# Roland_mem2.net
KiCad netlist of a schematic drawn in EAGLE
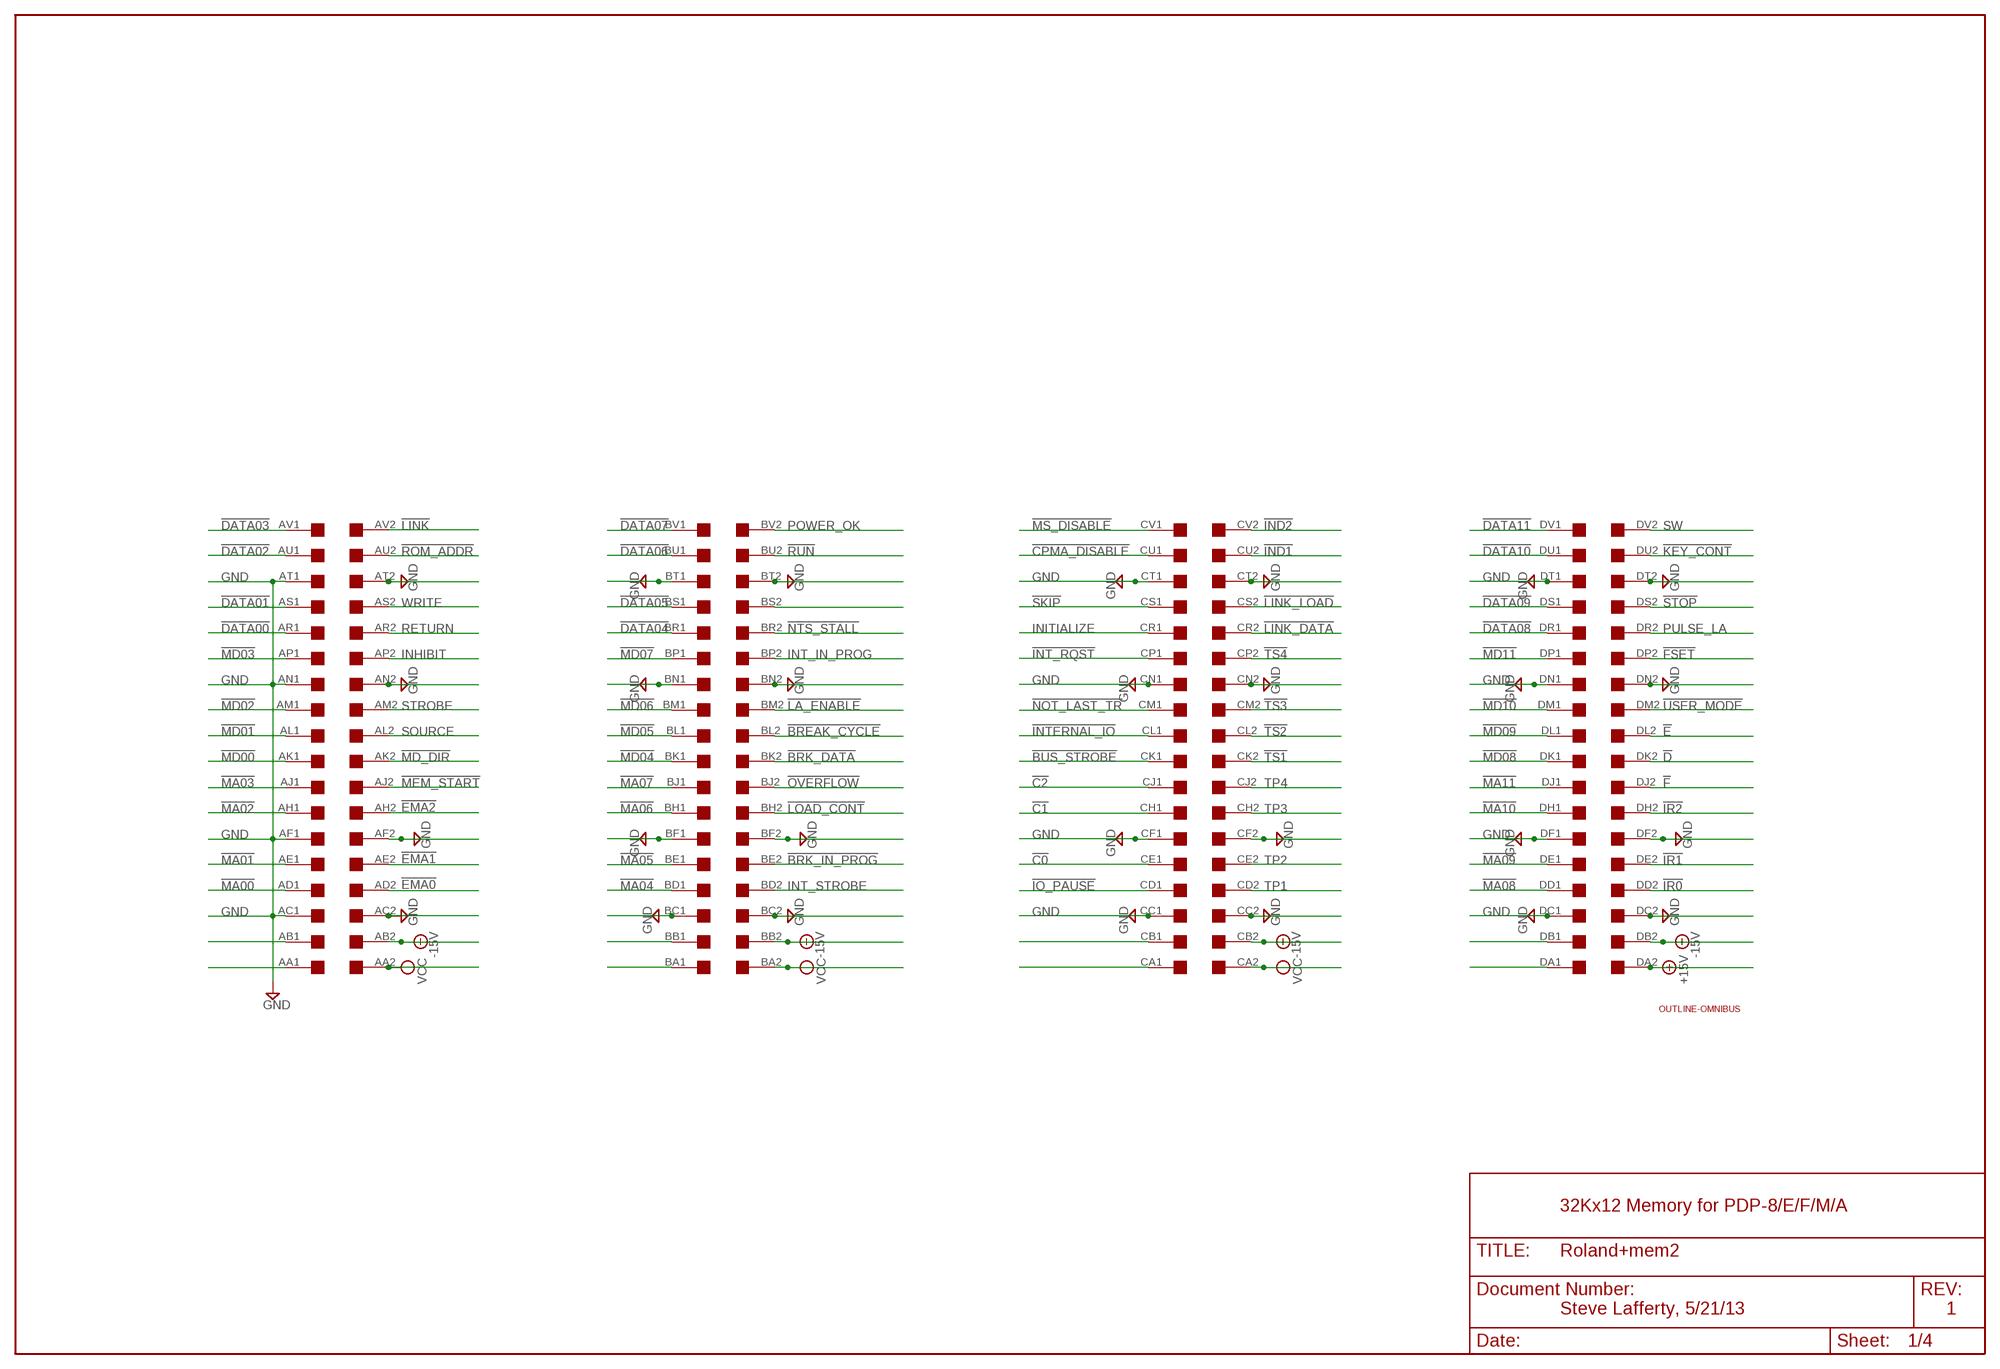
[diagram p0: schematic, sheet 1]
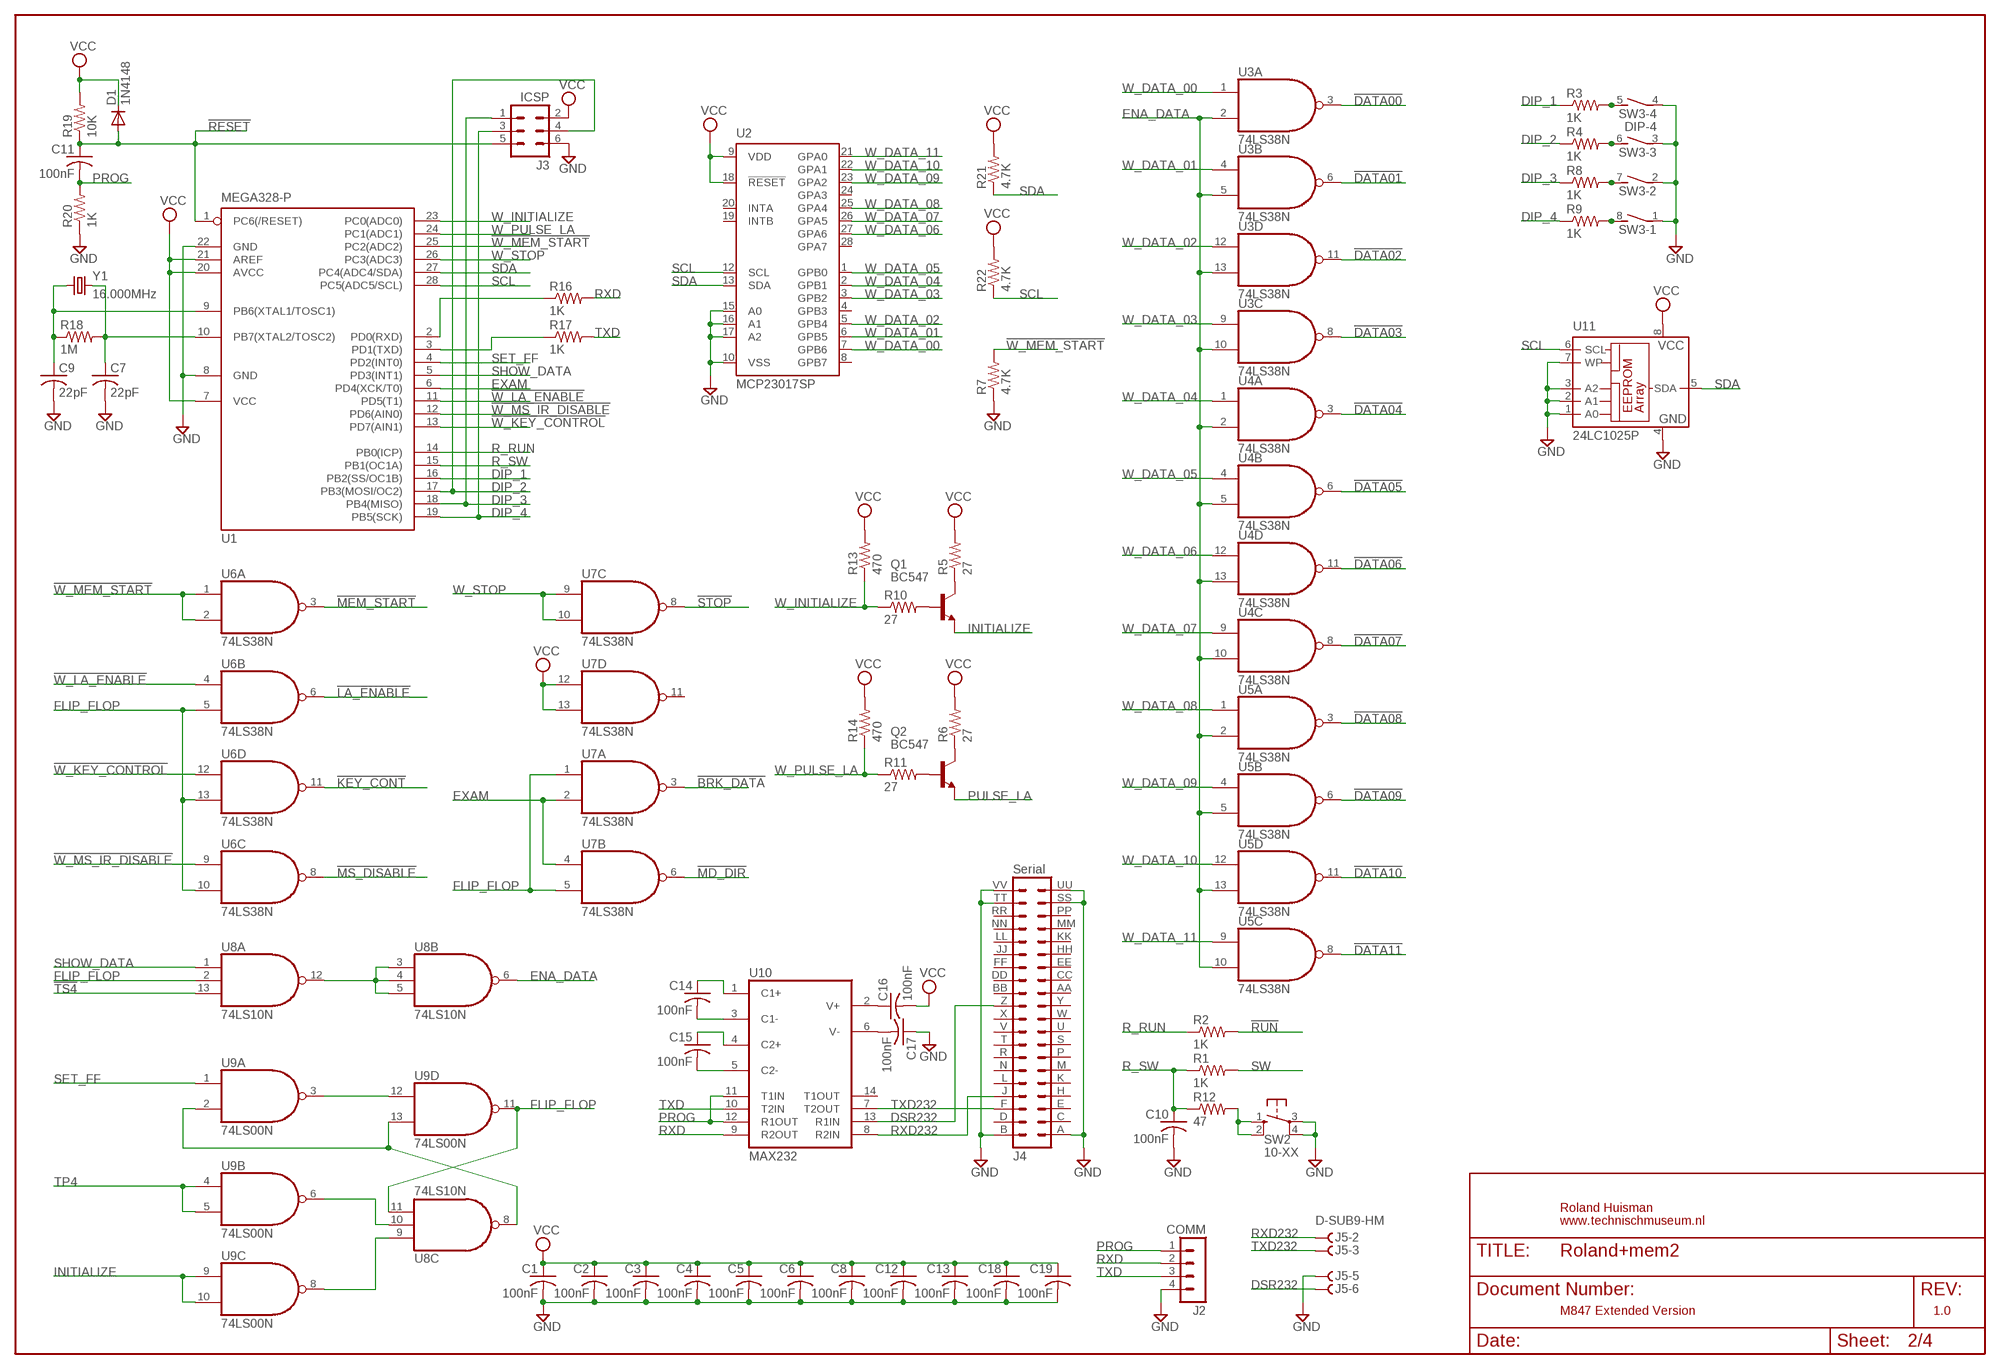
[diagram p1: schematic, sheet 2]
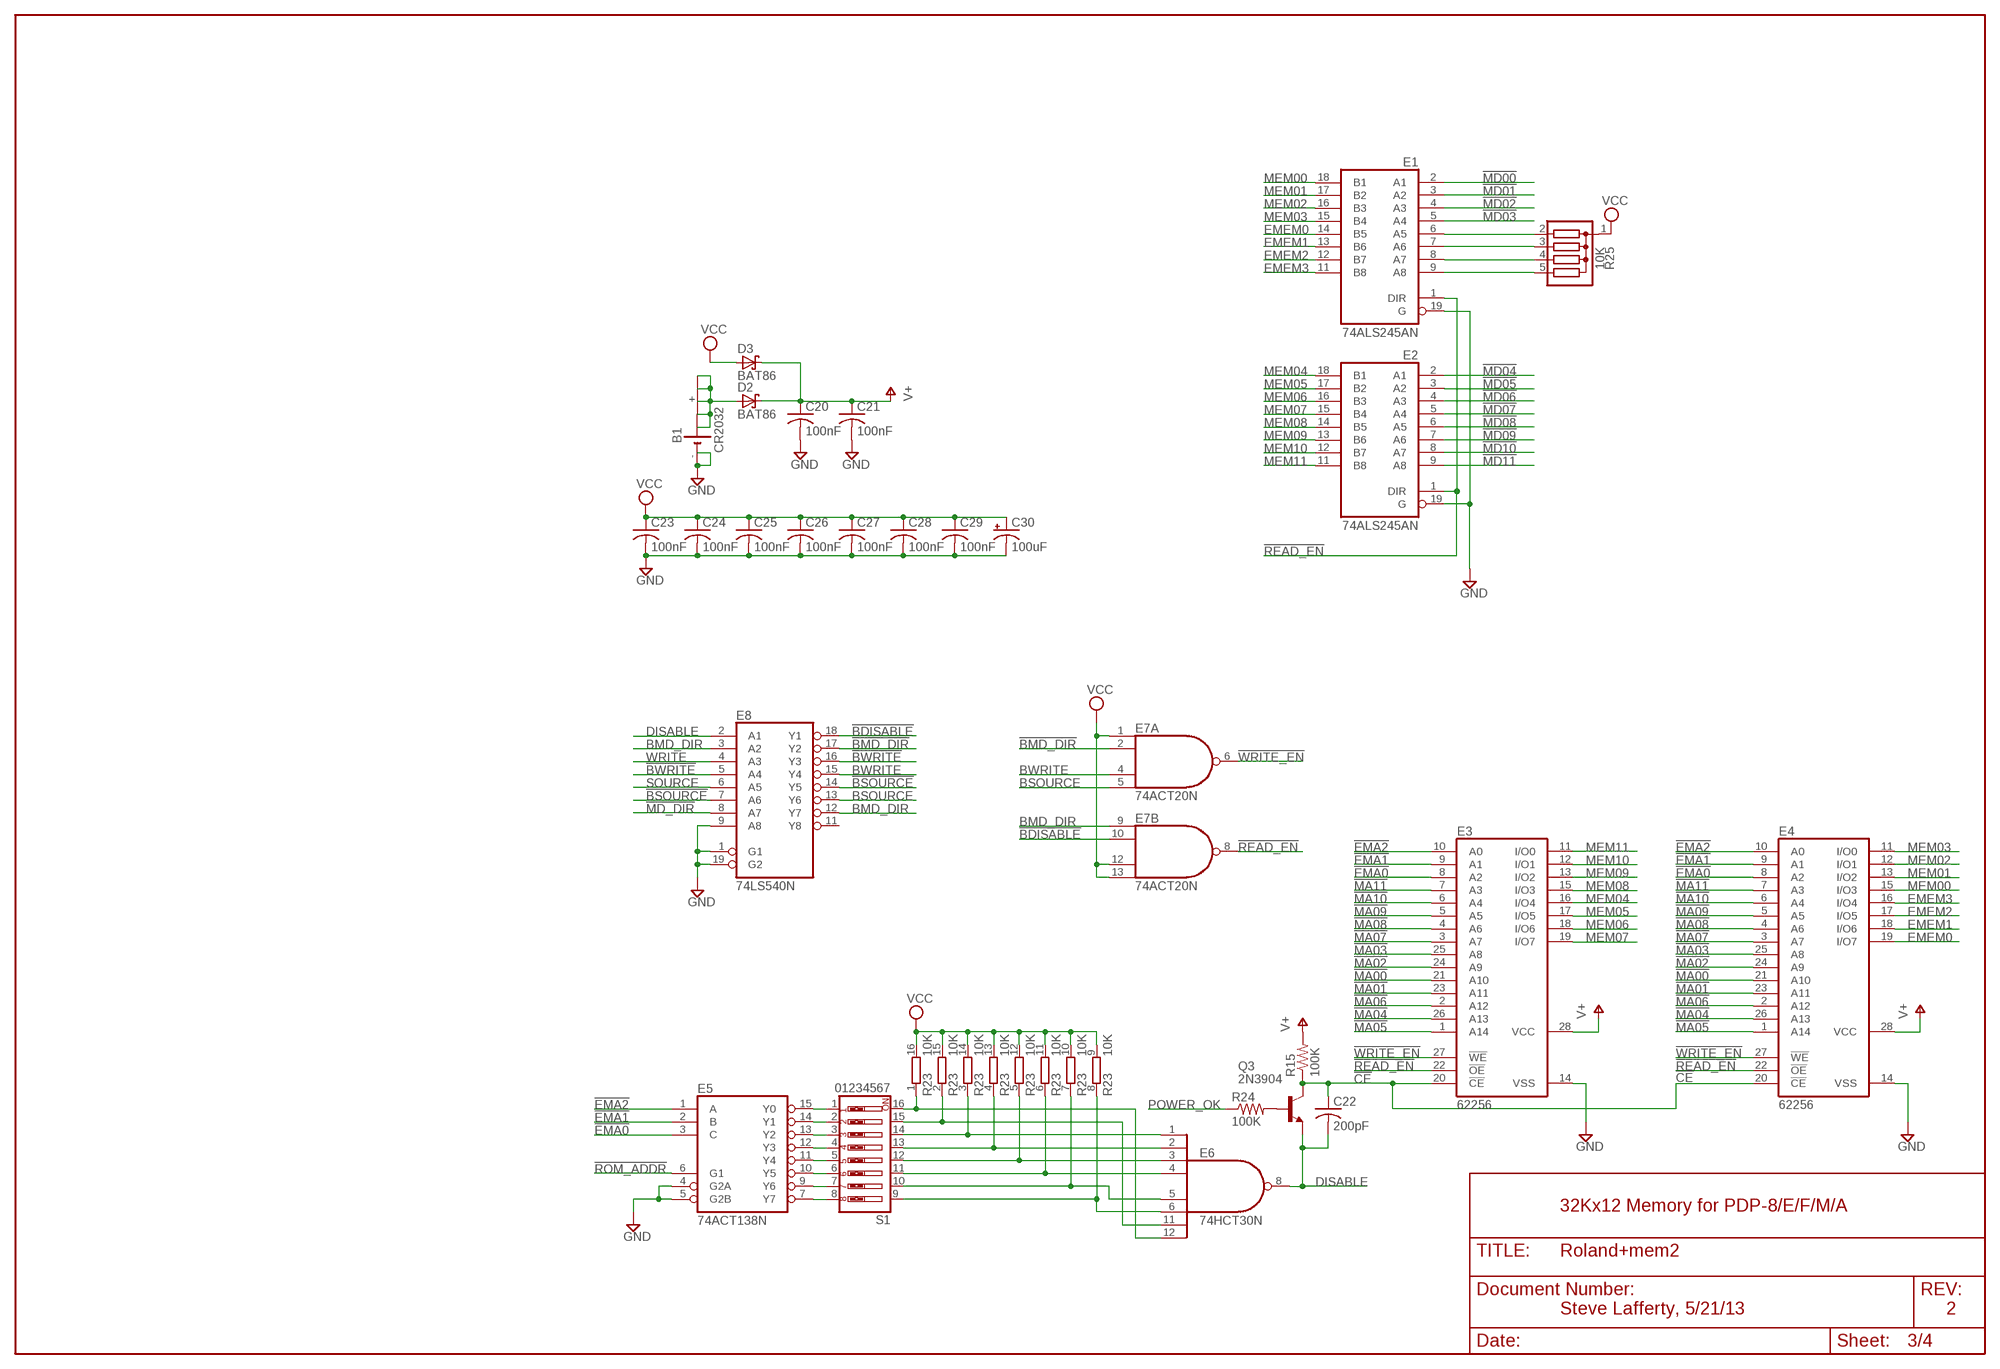
[diagram p2: schematic, sheet 3]
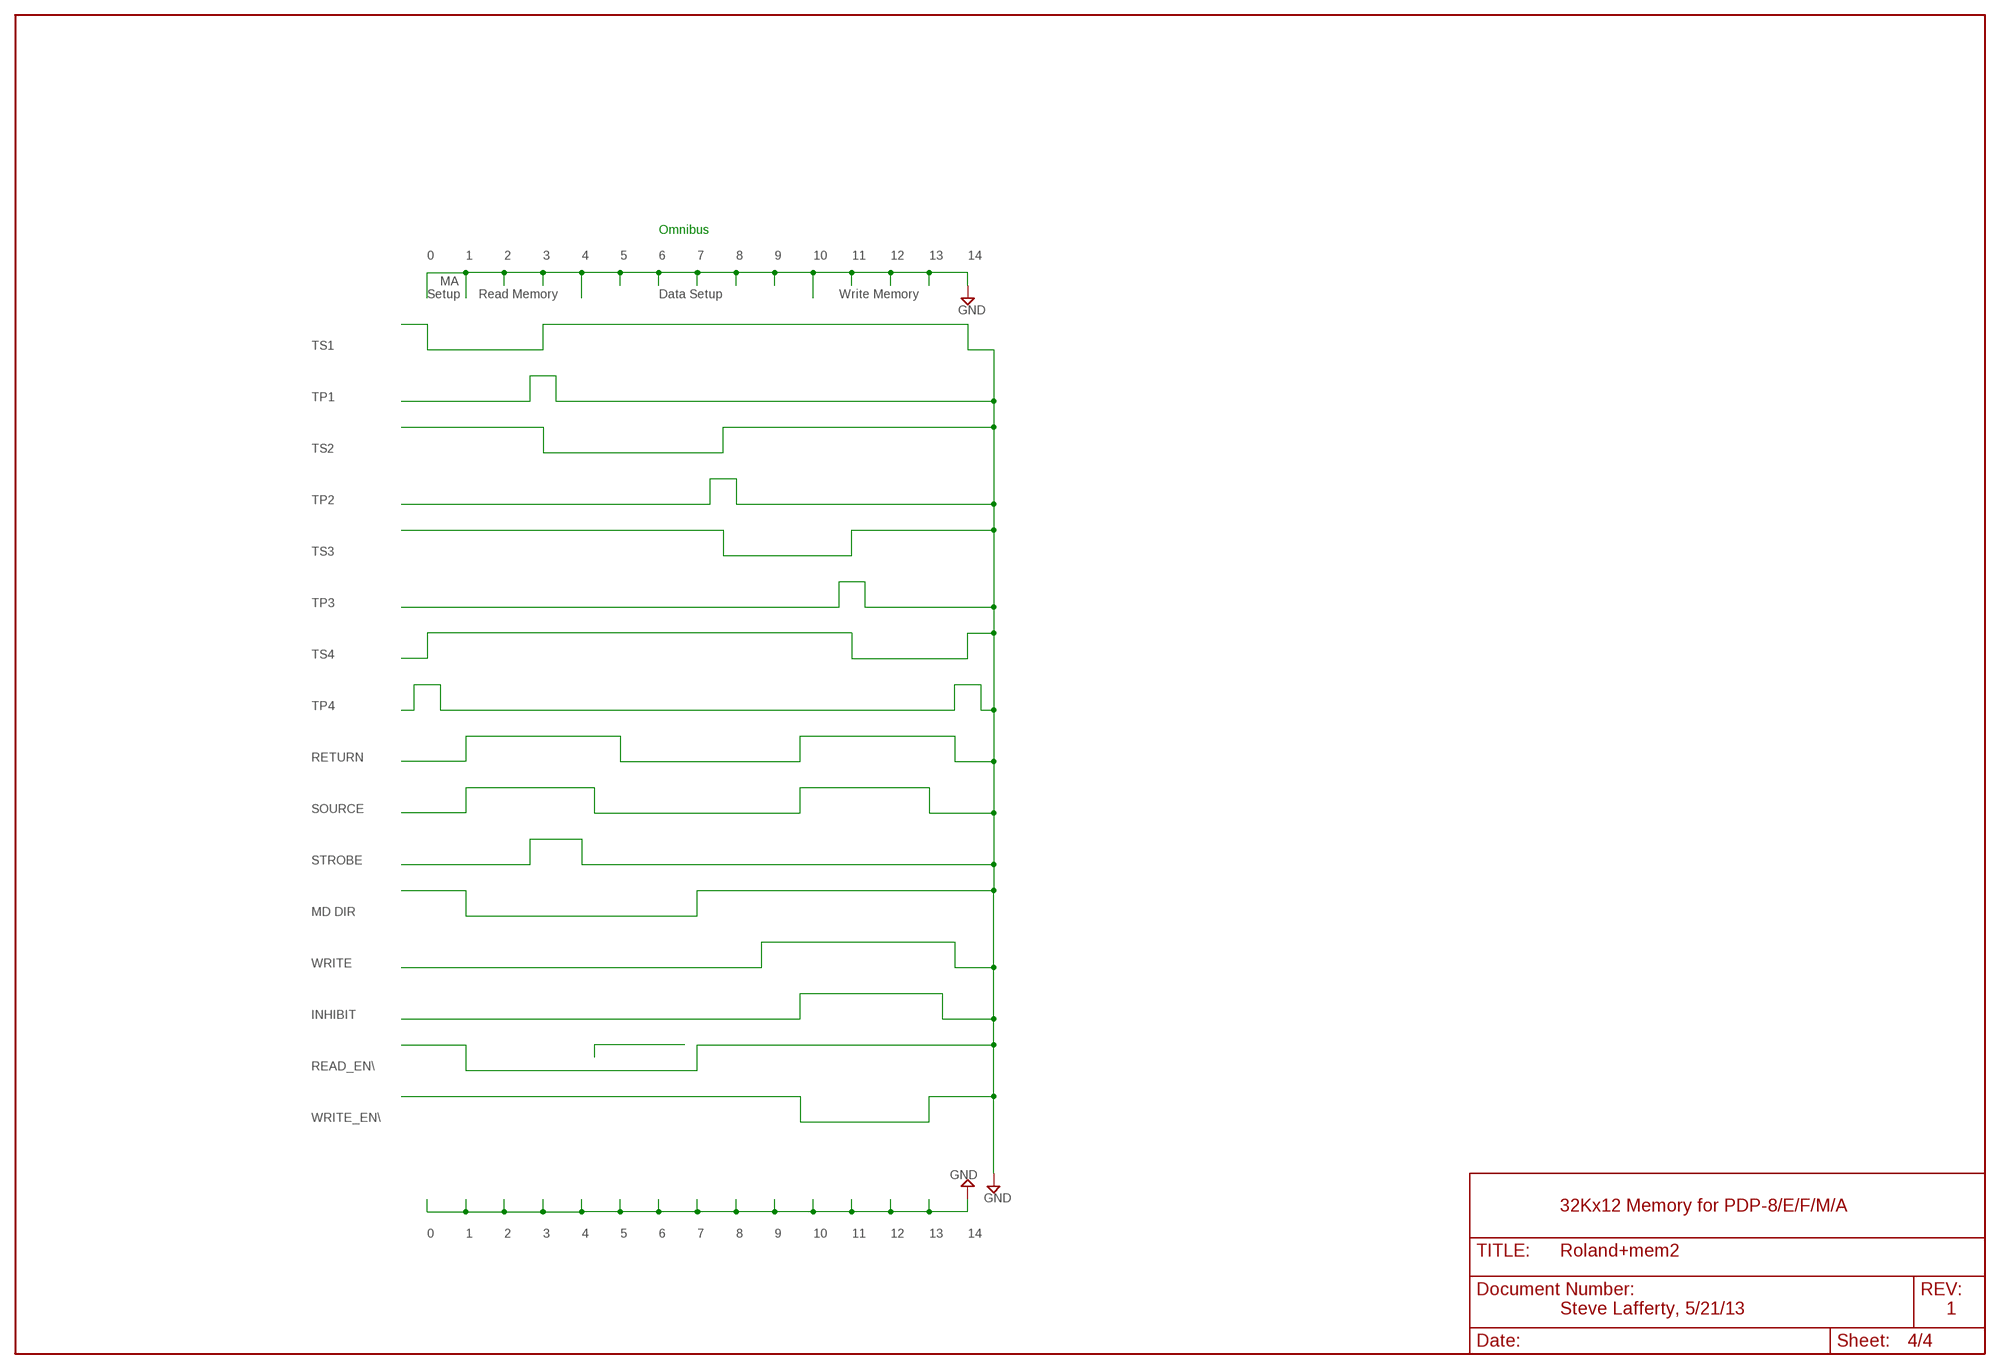
[diagram p3: schematic, sheet 4]

(export (version "E")
  (design (tool "Eeschema 10.0.6"))
  (components
    (comp (ref "C1")
      (value "100nF")
      (footprint "eagle-import:C050-025X075")
      (libsource (lib "eagle-import") (part "C-US050-025X075"))
    )
    (comp (ref "C2")
      (value "100nF")
      (footprint "eagle-import:C050-025X075")
      (libsource (lib "eagle-import") (part "C-US050-025X075"))
    )
    (comp (ref "C3")
      (value "100nF")
      (footprint "eagle-import:C050-025X075")
      (libsource (lib "eagle-import") (part "C-US050-025X075"))
    )
    (comp (ref "C4")
      (value "100nF")
      (footprint "eagle-import:C050-025X075")
      (libsource (lib "eagle-import") (part "C-US050-025X075"))
    )
    (comp (ref "C5")
      (value "100nF")
      (footprint "eagle-import:C050-025X075")
      (libsource (lib "eagle-import") (part "C-US050-025X075"))
    )
    (comp (ref "C6")
      (value "100nF")
      (footprint "eagle-import:C050-025X075")
      (libsource (lib "eagle-import") (part "C-US050-025X075"))
    )
    (comp (ref "C7")
      (value "22pF")
      (footprint "eagle-import:C050-025X075")
      (libsource (lib "eagle-import") (part "C-US050-025X075"))
    )
    (comp (ref "C8")
      (value "100nF")
      (footprint "eagle-import:C050-025X075")
      (libsource (lib "eagle-import") (part "C-US050-025X075"))
    )
    (comp (ref "C9")
      (value "22pF")
      (footprint "eagle-import:C050-025X075")
      (libsource (lib "eagle-import") (part "C-US050-025X075"))
    )
    (comp (ref "C10")
      (value "100nF")
      (footprint "eagle-import:C050-025X075")
      (libsource (lib "eagle-import") (part "C-US050-025X075"))
    )
    (comp (ref "C11")
      (value "100nF")
      (footprint "eagle-import:C050-025X075")
      (libsource (lib "eagle-import") (part "C-US050-025X075"))
    )
    (comp (ref "C12")
      (value "100nF")
      (footprint "eagle-import:C050-025X075")
      (libsource (lib "eagle-import") (part "C-US050-025X075"))
    )
    (comp (ref "C13")
      (value "100nF")
      (footprint "eagle-import:C050-025X075")
      (libsource (lib "eagle-import") (part "C-US050-025X075"))
    )
    (comp (ref "C14")
      (value "100nF")
      (footprint "eagle-import:C050-025X075")
      (libsource (lib "eagle-import") (part "C-US050-025X075"))
    )
    (comp (ref "C15")
      (value "100nF")
      (footprint "eagle-import:C050-025X075")
      (libsource (lib "eagle-import") (part "C-US050-025X075"))
    )
    (comp (ref "C16")
      (value "100nF")
      (footprint "eagle-import:C050-025X075")
      (libsource (lib "eagle-import") (part "C-US050-025X075"))
    )
    (comp (ref "C17")
      (value "100nF")
      (footprint "eagle-import:C050-025X075")
      (libsource (lib "eagle-import") (part "C-US050-025X075"))
    )
    (comp (ref "C18")
      (value "100nF")
      (footprint "eagle-import:C050-025X075")
      (libsource (lib "eagle-import") (part "C-US050-025X075"))
    )
    (comp (ref "C19")
      (value "100nF")
      (footprint "eagle-import:C050-025X075")
      (libsource (lib "eagle-import") (part "C-US050-025X075"))
    )
    (comp (ref "D1")
      (value "1N4148")
      (footprint "eagle-import:DO35-10")
      (libsource (lib "eagle-import") (part "1N4148DO35-10"))
    )
    (comp (ref "J2")
      (value "COMM")
      (footprint "eagle-import:MA04-1")
      (libsource (lib "eagle-import") (part "MA04-1"))
    )
    (comp (ref "J3")
      (value "ICSP")
      (footprint "eagle-import:MA03-2")
      (libsource (lib "eagle-import") (part "MA03-2"))
    )
    (comp (ref "J4")
      (value "Serial")
      (footprint "eagle-import:DEC40PINH")
      (libsource (lib "eagle-import") (part "DEC40PINH"))
    )
    (comp (ref "J5")
      (value "D-SUB9-HM")
      (footprint "eagle-import:H5M09RA")
      (libsource (lib "eagle-import") (part "D-SUB9-H5M09RA"))
    )
    (comp (ref "Q1")
      (value "BC547")
      (footprint "eagle-import:TO5")
      (libsource (lib "eagle-import") (part "-NPN-TO5"))
    )
    (comp (ref "Q2")
      (value "BC547")
      (footprint "eagle-import:TO5")
      (libsource (lib "eagle-import") (part "-NPN-TO5"))
    )
    (comp (ref "R1")
      (value "1K")
      (footprint "eagle-import:0207_10")
      (libsource (lib "eagle-import") (part "R-US_0207/10"))
    )
    (comp (ref "R2")
      (value "1K")
      (footprint "eagle-import:0207_10")
      (libsource (lib "eagle-import") (part "R-US_0207/10"))
    )
    (comp (ref "R3")
      (value "1K")
      (footprint "eagle-import:0207_10")
      (libsource (lib "eagle-import") (part "R-US_0207/10"))
    )
    (comp (ref "R4")
      (value "1K")
      (footprint "eagle-import:0207_10")
      (libsource (lib "eagle-import") (part "R-US_0207/10"))
    )
    (comp (ref "R5")
      (value "27")
      (footprint "eagle-import:0207_10")
      (libsource (lib "eagle-import") (part "R-US_0207/10"))
    )
    (comp (ref "R6")
      (value "27")
      (footprint "eagle-import:0207_10")
      (libsource (lib "eagle-import") (part "R-US_0207/10"))
    )
    (comp (ref "R7")
      (value "4.7K")
      (footprint "eagle-import:0207_10")
      (libsource (lib "eagle-import") (part "R-US_0207/10"))
    )
    (comp (ref "R8")
      (value "1K")
      (footprint "eagle-import:0207_10")
      (libsource (lib "eagle-import") (part "R-US_0207/10"))
    )
    (comp (ref "R9")
      (value "1K")
      (footprint "eagle-import:0207_10")
      (libsource (lib "eagle-import") (part "R-US_0207/10"))
    )
    (comp (ref "R10")
      (value "27")
      (footprint "eagle-import:0207_10")
      (libsource (lib "eagle-import") (part "R-US_0207/10"))
    )
    (comp (ref "R11")
      (value "27")
      (footprint "eagle-import:0207_10")
      (libsource (lib "eagle-import") (part "R-US_0207/10"))
    )
    (comp (ref "R12")
      (value "47")
      (footprint "eagle-import:0207_10")
      (libsource (lib "eagle-import") (part "R-US_0207/10"))
    )
    (comp (ref "R13")
      (value "470")
      (footprint "eagle-import:0207_10")
      (libsource (lib "eagle-import") (part "R-US_0207/10"))
    )
    (comp (ref "R14")
      (value "470")
      (footprint "eagle-import:0207_10")
      (libsource (lib "eagle-import") (part "R-US_0207/10"))
    )
    (comp (ref "R16")
      (value "1K")
      (footprint "eagle-import:0207_10")
      (libsource (lib "eagle-import") (part "R-US_0207/10"))
    )
    (comp (ref "R17")
      (value "1K")
      (footprint "eagle-import:0207_10")
      (libsource (lib "eagle-import") (part "R-US_0207/10"))
    )
    (comp (ref "R18")
      (value "1M")
      (footprint "eagle-import:0207_10")
      (libsource (lib "eagle-import") (part "R-US_0207/10"))
    )
    (comp (ref "R19")
      (value "10K")
      (footprint "eagle-import:0207_10")
      (libsource (lib "eagle-import") (part "R-US_0207/10"))
    )
    (comp (ref "R20")
      (value "1K")
      (footprint "eagle-import:0207_10")
      (libsource (lib "eagle-import") (part "R-US_0207/10"))
    )
    (comp (ref "R21")
      (value "4.7K")
      (footprint "eagle-import:0207_10")
      (libsource (lib "eagle-import") (part "R-US_0207/10"))
    )
    (comp (ref "R22")
      (value "4.7K")
      (footprint "eagle-import:0207_10")
      (libsource (lib "eagle-import") (part "R-US_0207/10"))
    )
    (comp (ref "SW2")
      (value "10-XX")
      (footprint "eagle-import:B3F-10XX")
      (fields (field (name "MPN") "B3F-1000"))
      (libsource (lib "eagle-import") (part "10-XX"))
    )
    (comp (ref "SW3")
      (value "DIP-4")
      (footprint "eagle-import:DIP04S")
      (libsource (lib "eagle-import") (part "DIP04S"))
    )
    (comp (ref "U1")
      (value "MEGA328-P")
      (footprint "eagle-import:DIL28-3")
      (libsource (lib "eagle-import") (part "MEGA8-P"))
    )
    (comp (ref "U2")
      (value "MCP23017SP")
      (footprint "eagle-import:DIL28-3")
      (fields (field (name "MF") "MICROCHIP") (field (name "MPN") "MCP23017-E/SP"))
      (libsource (lib "eagle-import") (part "MCP23017SP"))
    )
    (comp (ref "U3")
      (value "74LS38N")
      (footprint "eagle-import:DIL14")
      (libsource (lib "eagle-import") (part "7438NLS"))
    )
    (comp (ref "U4")
      (value "74LS38N")
      (footprint "eagle-import:DIL14")
      (libsource (lib "eagle-import") (part "7438NLS"))
    )
    (comp (ref "U5")
      (value "74LS38N")
      (footprint "eagle-import:DIL14")
      (libsource (lib "eagle-import") (part "7438NLS"))
    )
    (comp (ref "U6")
      (value "74LS38N")
      (footprint "eagle-import:DIL14")
      (libsource (lib "eagle-import") (part "7438NLS"))
    )
    (comp (ref "U7")
      (value "74LS38N")
      (footprint "eagle-import:DIL14")
      (libsource (lib "eagle-import") (part "7438NLS"))
    )
    (comp (ref "U8")
      (value "74LS10N")
      (footprint "eagle-import:DIL14")
      (libsource (lib "eagle-import") (part "7410NLS"))
    )
    (comp (ref "U9")
      (value "74LS00N")
      (footprint "eagle-import:DIL14")
      (libsource (lib "eagle-import") (part "7400NLS"))
    )
    (comp (ref "U10")
      (value "MAX232")
      (footprint "eagle-import:DIL16")
      (fields (field (name "MF") "MAXIM") (field (name "MPN") "MAX232ACPE+"))
      (libsource (lib "eagle-import") (part "MAX232"))
    )
    (comp (ref "U11")
      (value "24LC1025P")
      (footprint "eagle-import:DIL8")
      (fields (field (name "MF") "MICROCHIP") (field (name "MPN") "24LC025-I/P"))
      (libsource (lib "eagle-import") (part "24PLC025"))
    )
    (comp (ref "Y1")
      (value "16.000MHz")
      (footprint "eagle-import:HC49U-H")
      (libsource (lib "eagle-import") (part "CRYSTALHC49U-H"))
    )
    (comp (ref "J1")
      (value "EDGE")
      (footprint "eagle-import:EDGE-CON8")
      (libsource (lib "eagle-import") (part "QUAD"))
    )
    (comp (ref "U$1")
      (value "OUTLINE-OMNIBUS")
      (footprint "eagle-import:OMNIBUS")
      (libsource (lib "eagle-import") (part "OUTLINE-OMNIBUS"))
    )
    (comp (ref "B1")
      (value "CR2032")
      (footprint "eagle-import:B2430UNI")
      (libsource (lib "eagle-import") (part "B2430UNI"))
    )
    (comp (ref "C20")
      (value "100nF")
      (footprint "eagle-import:C050-025X075")
      (libsource (lib "eagle-import") (part "C-US050-025X075"))
    )
    (comp (ref "C21")
      (value "100nF")
      (footprint "eagle-import:C050-025X075")
      (libsource (lib "eagle-import") (part "C-US050-025X075"))
    )
    (comp (ref "C22")
      (value "200pF")
      (footprint "eagle-import:C050-025X075")
      (libsource (lib "eagle-import") (part "C-US050-025X075"))
    )
    (comp (ref "C23")
      (value "100nF")
      (footprint "eagle-import:C050-025X075")
      (libsource (lib "eagle-import") (part "C-US050-025X075"))
    )
    (comp (ref "C24")
      (value "100nF")
      (footprint "eagle-import:C050-025X075")
      (libsource (lib "eagle-import") (part "C-US050-025X075"))
    )
    (comp (ref "C25")
      (value "100nF")
      (footprint "eagle-import:C050-025X075")
      (libsource (lib "eagle-import") (part "C-US050-025X075"))
    )
    (comp (ref "C26")
      (value "100nF")
      (footprint "eagle-import:C050-025X075")
      (libsource (lib "eagle-import") (part "C-US050-025X075"))
    )
    (comp (ref "C27")
      (value "100nF")
      (footprint "eagle-import:C050-025X075")
      (libsource (lib "eagle-import") (part "C-US050-025X075"))
    )
    (comp (ref "C28")
      (value "100nF")
      (footprint "eagle-import:C050-025X075")
      (libsource (lib "eagle-import") (part "C-US050-025X075"))
    )
    (comp (ref "C29")
      (value "100nF")
      (footprint "eagle-import:C050-025X075")
      (libsource (lib "eagle-import") (part "C-US050-025X075"))
    )
    (comp (ref "C30")
      (value "100uF")
      (footprint "eagle-import:E12-8")
      (libsource (lib "eagle-import") (part "CPOL-USE20-8AXIAL"))
    )
    (comp (ref "D2")
      (value "BAT86")
      (footprint "eagle-import:DO35-10")
      (libsource (lib "eagle-import") (part "BAT19"))
    )
    (comp (ref "D3")
      (value "BAT86")
      (footprint "eagle-import:DO35-10")
      (libsource (lib "eagle-import") (part "BAT19"))
    )
    (comp (ref "E1")
      (value "74ALS245AN")
      (footprint "eagle-import:DIL20")
      (libsource (lib "eagle-import") (part "74245NLS"))
    )
    (comp (ref "E2")
      (value "74ALS245AN")
      (footprint "eagle-import:DIL20")
      (libsource (lib "eagle-import") (part "74245NLS"))
    )
    (comp (ref "E3")
      (value "62256")
      (footprint "eagle-import:DIL28-6")
      (libsource (lib "eagle-import") (part "58C256P"))
    )
    (comp (ref "E4")
      (value "62256")
      (footprint "eagle-import:DIL28-6")
      (libsource (lib "eagle-import") (part "58C256P"))
    )
    (comp (ref "E5")
      (value "74ACT138N")
      (footprint "eagle-import:DIL16")
      (libsource (lib "eagle-import") (part "74138NLS"))
    )
    (comp (ref "E6")
      (value "74HCT30N")
      (footprint "eagle-import:DIL14")
      (libsource (lib "eagle-import") (part "7430NLS"))
    )
    (comp (ref "E7")
      (value "74ACT20N")
      (footprint "eagle-import:DIL14")
      (libsource (lib "eagle-import") (part "7420NLS"))
    )
    (comp (ref "E8")
      (value "74LS540N")
      (footprint "eagle-import:DIL20")
      (libsource (lib "eagle-import") (part "74540NLS"))
    )
    (comp (ref "Q3")
      (value "2N3904")
      (footprint "eagle-import:TO92")
      (libsource (lib "eagle-import") (part "2N3904"))
    )
    (comp (ref "R15")
      (value "100K")
      (footprint "eagle-import:0207_10")
      (libsource (lib "eagle-import") (part "R-US_0207/10"))
    )
    (comp (ref "R23")
      (value "10K")
      (footprint "eagle-import:DIL16")
      (libsource (lib "eagle-import") (part "8R-P"))
    )
    (comp (ref "R24")
      (value "100K")
      (footprint "eagle-import:0207_10")
      (libsource (lib "eagle-import") (part "R-US_0207/10"))
    )
    (comp (ref "R25")
      (value "10K")
      (footprint "eagle-import:SIL5")
      (libsource (lib "eagle-import") (part "G04R"))
    )
    (comp (ref "S1")
      (value "01234567")
      (footprint "eagle-import:EDG-08")
      (libsource (lib "eagle-import") (part "SW_DIP-8"))
    )
  )
  (nets
    (net (code "1") (name "+15V") (class "Default")
      (node (ref "J1") (pin "DA2") (pinfunction "1_DA2") (pintype "bidirectional"))
    )
    (net (code "2") (name "-15V") (class "Default")
      (node (ref "J1") (pin "AB2") (pinfunction "1_AB2") (pintype "bidirectional"))
      (node (ref "J1") (pin "BB2") (pinfunction "1_BB2") (pintype "bidirectional"))
      (node (ref "J1") (pin "CB2") (pinfunction "1_CB2") (pintype "bidirectional"))
      (node (ref "J1") (pin "DB2") (pinfunction "1_DB2") (pintype "bidirectional"))
    )
    (net (code "3") (name "BMD_DIR") (class "Default")
      (node (ref "E7") (pin "9") (pinfunction "I0_9") (pintype "input"))
      (node (ref "E8") (pin "12") (pinfunction "Y7_12") (pintype "tri_state"))
      (node (ref "E8") (pin "3") (pinfunction "A2_3") (pintype "input"))
    )
    (net (code "4") (name "BSOURCE") (class "Default")
      (node (ref "E7") (pin "5") (pinfunction "I3_5") (pintype "input"))
      (node (ref "E8") (pin "13") (pinfunction "Y6_13") (pintype "tri_state"))
    )
    (net (code "5") (name "BWRITE") (class "Default")
      (node (ref "E7") (pin "4") (pinfunction "I2_4") (pintype "input"))
      (node (ref "E8") (pin "15") (pinfunction "Y4_15") (pintype "tri_state"))
    )
    (net (code "6") (name "DIP_1") (class "Default")
      (node (ref "R3") (pin "1") (pinfunction "1_1") (pintype "passive"))
      (node (ref "U1") (pin "16") (pinfunction "PB2(SS/OC1B)_16") (pintype "bidirectional"))
    )
    (net (code "7") (name "DIP_2") (class "Default")
      (node (ref "J3") (pin "4") (pinfunction "4_4") (pintype "passive"))
      (node (ref "R4") (pin "1") (pinfunction "1_1") (pintype "passive"))
      (node (ref "U1") (pin "17") (pinfunction "PB3(MOSI/OC2)_17") (pintype "bidirectional"))
    )
    (net (code "8") (name "DIP_3") (class "Default")
      (node (ref "J3") (pin "1") (pinfunction "1_1") (pintype "passive"))
      (node (ref "R8") (pin "1") (pinfunction "1_1") (pintype "passive"))
      (node (ref "U1") (pin "18") (pinfunction "PB4(MISO)_18") (pintype "bidirectional"))
    )
    (net (code "9") (name "DIP_4") (class "Default")
      (node (ref "J3") (pin "3") (pinfunction "3_3") (pintype "passive"))
      (node (ref "R9") (pin "1") (pinfunction "1_1") (pintype "passive"))
      (node (ref "U1") (pin "19") (pinfunction "PB5(SCK)_19") (pintype "bidirectional"))
    )
    (net (code "10") (name "DISABLE") (class "Default")
      (node (ref "C22") (pin "2") (pinfunction "2_2") (pintype "passive"))
      (node (ref "E6") (pin "8") (pinfunction "O_8") (pintype "output"))
      (node (ref "E8") (pin "2") (pinfunction "A1_2") (pintype "input"))
      (node (ref "Q3") (pin "3") (pinfunction "E_3") (pintype "passive"))
    )
    (net (code "11") (name "DSR232") (class "Default")
      (node (ref "J4") (pin "Z") (pinfunction "22_Z") (pintype "bidirectional"))
      (node (ref "J5") (pin "6") (pinfunction "F_6") (pintype "passive"))
      (node (ref "U10") (pin "13") (pinfunction "R1IN_13") (pintype "input"))
    )
    (net (code "12") (name "EMEM0") (class "Default")
      (node (ref "E1") (pin "14") (pinfunction "B5_14") (pintype "bidirectional"))
      (node (ref "E4") (pin "19") (pinfunction "I/O7_19") (pintype "tri_state"))
    )
    (net (code "13") (name "EMEM1") (class "Default")
      (node (ref "E1") (pin "13") (pinfunction "B6_13") (pintype "bidirectional"))
      (node (ref "E4") (pin "18") (pinfunction "I/O6_18") (pintype "tri_state"))
    )
    (net (code "14") (name "EMEM2") (class "Default")
      (node (ref "E1") (pin "12") (pinfunction "B7_12") (pintype "bidirectional"))
      (node (ref "E4") (pin "17") (pinfunction "I/O5_17") (pintype "tri_state"))
    )
    (net (code "15") (name "EMEM3") (class "Default")
      (node (ref "E1") (pin "11") (pinfunction "B8_11") (pintype "bidirectional"))
      (node (ref "E4") (pin "16") (pinfunction "I/O4_16") (pintype "tri_state"))
    )
    (net (code "16") (name "ENA_DATA") (class "Default")
      (node (ref "U3") (pin "10") (pinfunction "I1_10") (pintype "input"))
      (node (ref "U3") (pin "13") (pinfunction "I1_13") (pintype "input"))
      (node (ref "U3") (pin "2") (pinfunction "I1_2") (pintype "input"))
      (node (ref "U3") (pin "5") (pinfunction "I1_5") (pintype "input"))
      (node (ref "U4") (pin "10") (pinfunction "I1_10") (pintype "input"))
      (node (ref "U4") (pin "13") (pinfunction "I1_13") (pintype "input"))
      (node (ref "U4") (pin "2") (pinfunction "I1_2") (pintype "input"))
      (node (ref "U4") (pin "5") (pinfunction "I1_5") (pintype "input"))
      (node (ref "U5") (pin "10") (pinfunction "I1_10") (pintype "input"))
      (node (ref "U5") (pin "13") (pinfunction "I1_13") (pintype "input"))
      (node (ref "U5") (pin "2") (pinfunction "I1_2") (pintype "input"))
      (node (ref "U5") (pin "5") (pinfunction "I1_5") (pintype "input"))
      (node (ref "U8") (pin "6") (pinfunction "O_6") (pintype "output"))
    )
    (net (code "17") (name "EXAM") (class "Default")
      (node (ref "U1") (pin "6") (pinfunction "PD4(XCK/T0)_6") (pintype "bidirectional"))
      (node (ref "U7") (pin "2") (pinfunction "I1_2") (pintype "input"))
      (node (ref "U7") (pin "4") (pinfunction "I0_4") (pintype "input"))
    )
    (net (code "18") (name "FLIP_FLOP") (class "Default")
      (node (ref "U6") (pin "10") (pinfunction "I1_10") (pintype "input"))
      (node (ref "U6") (pin "13") (pinfunction "I1_13") (pintype "input"))
      (node (ref "U6") (pin "5") (pinfunction "I1_5") (pintype "input"))
      (node (ref "U7") (pin "1") (pinfunction "I0_1") (pintype "input"))
      (node (ref "U7") (pin "5") (pinfunction "I1_5") (pintype "input"))
      (node (ref "U8") (pin "11") (pinfunction "I2_11") (pintype "input"))
      (node (ref "U8") (pin "2") (pinfunction "I1_2") (pintype "input"))
      (node (ref "U9") (pin "11") (pinfunction "O_11") (pintype "output"))
    )
    (net (code "19") (name "GND") (class "Default")
      (node (ref "B1") (pin "-") (pinfunction "-_-") (pintype "passive"))
      (node (ref "B1") (pin "-@1") (pinfunction "-_-@1") (pintype "passive"))
      (node (ref "C1") (pin "2") (pinfunction "2_2") (pintype "passive"))
      (node (ref "C10") (pin "2") (pinfunction "2_2") (pintype "passive"))
      (node (ref "C12") (pin "2") (pinfunction "2_2") (pintype "passive"))
      (node (ref "C13") (pin "2") (pinfunction "2_2") (pintype "passive"))
      (node (ref "C17") (pin "1") (pinfunction "1_1") (pintype "passive"))
      (node (ref "C18") (pin "2") (pinfunction "2_2") (pintype "passive"))
      (node (ref "C19") (pin "2") (pinfunction "2_2") (pintype "passive"))
      (node (ref "C2") (pin "2") (pinfunction "2_2") (pintype "passive"))
      (node (ref "C20") (pin "2") (pinfunction "2_2") (pintype "passive"))
      (node (ref "C21") (pin "2") (pinfunction "2_2") (pintype "passive"))
      (node (ref "C23") (pin "2") (pinfunction "2_2") (pintype "passive"))
      (node (ref "C24") (pin "2") (pinfunction "2_2") (pintype "passive"))
      (node (ref "C25") (pin "2") (pinfunction "2_2") (pintype "passive"))
      (node (ref "C26") (pin "2") (pinfunction "2_2") (pintype "passive"))
      (node (ref "C27") (pin "2") (pinfunction "2_2") (pintype "passive"))
      (node (ref "C28") (pin "2") (pinfunction "2_2") (pintype "passive"))
      (node (ref "C29") (pin "2") (pinfunction "2_2") (pintype "passive"))
      (node (ref "C3") (pin "2") (pinfunction "2_2") (pintype "passive"))
      (node (ref "C30") (pin "-") (pinfunction "-_-") (pintype "passive"))
      (node (ref "C4") (pin "2") (pinfunction "2_2") (pintype "passive"))
      (node (ref "C5") (pin "2") (pinfunction "2_2") (pintype "passive"))
      (node (ref "C6") (pin "2") (pinfunction "2_2") (pintype "passive"))
      (node (ref "C7") (pin "2") (pinfunction "2_2") (pintype "passive"))
      (node (ref "C8") (pin "2") (pinfunction "2_2") (pintype "passive"))
      (node (ref "C9") (pin "2") (pinfunction "2_2") (pintype "passive"))
      (node (ref "E1") (pin "19") (pinfunction "G_19") (pintype "input"))
      (node (ref "E2") (pin "19") (pinfunction "G_19") (pintype "input"))
      (node (ref "E3") (pin "14") (pinfunction "VSS_14") (pintype "power_in"))
      (node (ref "E4") (pin "14") (pinfunction "VSS_14") (pintype "power_in"))
      (node (ref "E5") (pin "4") (pinfunction "G2A_4") (pintype "input"))
      (node (ref "E5") (pin "5") (pinfunction "G2B_5") (pintype "input"))
      (node (ref "E8") (pin "1") (pinfunction "G1_1") (pintype "input"))
      (node (ref "E8") (pin "19") (pinfunction "G2_19") (pintype "input"))
      (node (ref "E8") (pin "9") (pinfunction "A8_9") (pintype "input"))
      (node (ref "J1") (pin "AC1") (pinfunction "1_AC1") (pintype "bidirectional"))
      (node (ref "J1") (pin "AC2") (pinfunction "1_AC2") (pintype "bidirectional"))
      (node (ref "J1") (pin "AF1") (pinfunction "1_AF1") (pintype "bidirectional"))
      (node (ref "J1") (pin "AF2") (pinfunction "1_AF2") (pintype "bidirectional"))
      (node (ref "J1") (pin "AN1") (pinfunction "1_AN1") (pintype "bidirectional"))
      (node (ref "J1") (pin "AN2") (pinfunction "1_AN2") (pintype "bidirectional"))
      (node (ref "J1") (pin "AT1") (pinfunction "1_AT1") (pintype "bidirectional"))
      (node (ref "J1") (pin "AT2") (pinfunction "1_AT2") (pintype "bidirectional"))
      (node (ref "J1") (pin "BC1") (pinfunction "1_BC1") (pintype "bidirectional"))
      (node (ref "J1") (pin "BC2") (pinfunction "1_BC2") (pintype "bidirectional"))
      (node (ref "J1") (pin "BF1") (pinfunction "1_BF1") (pintype "bidirectional"))
      (node (ref "J1") (pin "BF2") (pinfunction "1_BF2") (pintype "bidirectional"))
      (node (ref "J1") (pin "BN1") (pinfunction "1_BN1") (pintype "bidirectional"))
      (node (ref "J1") (pin "BN2") (pinfunction "1_BN2") (pintype "bidirectional"))
      (node (ref "J1") (pin "BT1") (pinfunction "1_BT1") (pintype "bidirectional"))
      (node (ref "J1") (pin "BT2") (pinfunction "1_BT2") (pintype "bidirectional"))
      (node (ref "J1") (pin "CC1") (pinfunction "1_CC1") (pintype "bidirectional"))
      (node (ref "J1") (pin "CC2") (pinfunction "1_CC2") (pintype "bidirectional"))
      (node (ref "J1") (pin "CF1") (pinfunction "1_CF1") (pintype "bidirectional"))
      (node (ref "J1") (pin "CF2") (pinfunction "1_CF2") (pintype "bidirectional"))
      (node (ref "J1") (pin "CN1") (pinfunction "1_CN1") (pintype "bidirectional"))
      (node (ref "J1") (pin "CN2") (pinfunction "1_CN2") (pintype "bidirectional"))
      (node (ref "J1") (pin "CT1") (pinfunction "1_CT1") (pintype "bidirectional"))
      (node (ref "J1") (pin "CT2") (pinfunction "1_CT2") (pintype "bidirectional"))
      (node (ref "J1") (pin "DC1") (pinfunction "1_DC1") (pintype "bidirectional"))
      (node (ref "J1") (pin "DC2") (pinfunction "1_DC2") (pintype "bidirectional"))
      (node (ref "J1") (pin "DF1") (pinfunction "1_DF1") (pintype "bidirectional"))
      (node (ref "J1") (pin "DF2") (pinfunction "1_DF2") (pintype "bidirectional"))
      (node (ref "J1") (pin "DN1") (pinfunction "1_DN1") (pintype "bidirectional"))
      (node (ref "J1") (pin "DN2") (pinfunction "1_DN2") (pintype "bidirectional"))
      (node (ref "J1") (pin "DT1") (pinfunction "1_DT1") (pintype "bidirectional"))
      (node (ref "J1") (pin "DT2") (pinfunction "1_DT2") (pintype "bidirectional"))
      (node (ref "J2") (pin "4") (pinfunction "4_4") (pintype "passive"))
      (node (ref "J3") (pin "6") (pinfunction "6_6") (pintype "passive"))
      (node (ref "J4") (pin "A") (pinfunction "1_A") (pintype "bidirectional"))
      (node (ref "J4") (pin "B") (pinfunction "2_B") (pintype "bidirectional"))
      (node (ref "J4") (pin "SS") (pinfunction "37_SS") (pintype "bidirectional"))
      (node (ref "J4") (pin "TT") (pinfunction "38_TT") (pintype "bidirectional"))
      (node (ref "J4") (pin "UU") (pinfunction "39_UU") (pintype "bidirectional"))
      (node (ref "J4") (pin "VV") (pinfunction "40_VV") (pintype "bidirectional"))
      (node (ref "J5") (pin "5") (pinfunction "F_5") (pintype "passive"))
      (node (ref "R20") (pin "1") (pinfunction "1_1") (pintype "passive"))
      (node (ref "R7") (pin "1") (pinfunction "1_1") (pintype "passive"))
      (node (ref "SW2") (pin "3") (pinfunction "P_3") (pintype "passive"))
      (node (ref "SW2") (pin "4") (pinfunction "P1_4") (pintype "passive"))
      (node (ref "SW3") (pin "1") (pinfunction "1_1") (pintype "passive"))
      (node (ref "SW3") (pin "2") (pinfunction "1_2") (pintype "passive"))
      (node (ref "SW3") (pin "3") (pinfunction "1_3") (pintype "passive"))
      (node (ref "SW3") (pin "4") (pinfunction "1_4") (pintype "passive"))
      (node (ref "U1") (pin "22") (pinfunction "GND_22") (pintype "power_in"))
      (node (ref "U1") (pin "8") (pinfunction "GND_8") (pintype "power_in"))
      (node (ref "U11") (pin "1") (pinfunction "A0_1") (pintype "input"))
      (node (ref "U11") (pin "2") (pinfunction "A1_2") (pintype "input"))
      (node (ref "U11") (pin "3") (pinfunction "A2_3") (pintype "input"))
      (node (ref "U11") (pin "4") (pinfunction "GND_4") (pintype "power_in"))
      (node (ref "U11") (pin "7") (pinfunction "WP_7") (pintype "input"))
      (node (ref "U2") (pin "10") (pinfunction "VSS_10") (pintype "power_in"))
      (node (ref "U2") (pin "15") (pinfunction "A0_15") (pintype "input"))
      (node (ref "U2") (pin "16") (pinfunction "A1_16") (pintype "input"))
      (node (ref "U2") (pin "17") (pinfunction "A2_17") (pintype "input"))
    )
    (net (code "20") (name "INHIBIT") (class "Default")
      (node (ref "J1") (pin "AP2") (pinfunction "1_AP2") (pintype "bidirectional"))
    )
    (net (code "21") (name "INITIALIZE") (class "Default")
      (node (ref "J1") (pin "CR1") (pinfunction "1_CR1") (pintype "bidirectional"))
      (node (ref "Q1") (pin "1") (pinfunction "E_1") (pintype "passive"))
      (node (ref "U9") (pin "10") (pinfunction "I1_10") (pintype "input"))
      (node (ref "U9") (pin "9") (pinfunction "I0_9") (pintype "input"))
    )
    (net (code "22") (name "INT_IN_PROG") (class "Default")
      (node (ref "J1") (pin "BP2") (pinfunction "1_BP2") (pintype "bidirectional"))
    )
    (net (code "23") (name "INT_STROBE") (class "Default")
      (node (ref "J1") (pin "BD2") (pinfunction "1_BD2") (pintype "bidirectional"))
    )
    (net (code "24") (name "MEM00") (class "Default")
      (node (ref "E1") (pin "18") (pinfunction "B1_18") (pintype "bidirectional"))
      (node (ref "E4") (pin "15") (pinfunction "I/O3_15") (pintype "tri_state"))
    )
    (net (code "25") (name "MEM01") (class "Default")
      (node (ref "E1") (pin "17") (pinfunction "B2_17") (pintype "bidirectional"))
      (node (ref "E4") (pin "13") (pinfunction "I/O2_13") (pintype "tri_state"))
    )
    (net (code "26") (name "MEM02") (class "Default")
      (node (ref "E1") (pin "16") (pinfunction "B3_16") (pintype "bidirectional"))
      (node (ref "E4") (pin "12") (pinfunction "I/O1_12") (pintype "tri_state"))
    )
    (net (code "27") (name "MEM03") (class "Default")
      (node (ref "E1") (pin "15") (pinfunction "B4_15") (pintype "bidirectional"))
      (node (ref "E4") (pin "11") (pinfunction "I/O0_11") (pintype "tri_state"))
    )
    (net (code "28") (name "MEM04") (class "Default")
      (node (ref "E2") (pin "18") (pinfunction "B1_18") (pintype "bidirectional"))
      (node (ref "E3") (pin "16") (pinfunction "I/O4_16") (pintype "tri_state"))
    )
    (net (code "29") (name "MEM05") (class "Default")
      (node (ref "E2") (pin "17") (pinfunction "B2_17") (pintype "bidirectional"))
      (node (ref "E3") (pin "17") (pinfunction "I/O5_17") (pintype "tri_state"))
    )
    (net (code "30") (name "MEM06") (class "Default")
      (node (ref "E2") (pin "16") (pinfunction "B3_16") (pintype "bidirectional"))
      (node (ref "E3") (pin "18") (pinfunction "I/O6_18") (pintype "tri_state"))
    )
    (net (code "31") (name "MEM07") (class "Default")
      (node (ref "E2") (pin "15") (pinfunction "B4_15") (pintype "bidirectional"))
      (node (ref "E3") (pin "19") (pinfunction "I/O7_19") (pintype "tri_state"))
    )
    (net (code "32") (name "MEM08") (class "Default")
      (node (ref "E2") (pin "14") (pinfunction "B5_14") (pintype "bidirectional"))
      (node (ref "E3") (pin "15") (pinfunction "I/O3_15") (pintype "tri_state"))
    )
    (net (code "33") (name "MEM09") (class "Default")
      (node (ref "E2") (pin "13") (pinfunction "B6_13") (pintype "bidirectional"))
      (node (ref "E3") (pin "13") (pinfunction "I/O2_13") (pintype "tri_state"))
    )
    (net (code "34") (name "MEM10") (class "Default")
      (node (ref "E2") (pin "12") (pinfunction "B7_12") (pintype "bidirectional"))
      (node (ref "E3") (pin "12") (pinfunction "I/O1_12") (pintype "tri_state"))
    )
    (net (code "35") (name "MEM11") (class "Default")
      (node (ref "E2") (pin "11") (pinfunction "B8_11") (pintype "bidirectional"))
      (node (ref "E3") (pin "11") (pinfunction "I/O0_11") (pintype "tri_state"))
    )
    (net (code "36") (name "Net-(B1-+-Pad+@1)") (class "Default")
      (node (ref "B1") (pin "+") (pinfunction "+_+") (pintype "passive"))
      (node (ref "B1") (pin "+@1") (pinfunction "+_+@1") (pintype "passive"))
      (node (ref "B1") (pin "+@2") (pinfunction "+_+@2") (pintype "passive"))
      (node (ref "B1") (pin "+@3") (pinfunction "+_+@3") (pintype "passive"))
      (node (ref "B1") (pin "+@4") (pinfunction "+_+@4") (pintype "passive"))
      (node (ref "D2") (pin "A") (pinfunction "A_A") (pintype "passive"))
    )
    (net (code "37") (name "Net-(E1A-A5)") (class "Default")
      (node (ref "E1") (pin "6") (pinfunction "A5_6") (pintype "bidirectional"))
      (node (ref "R25") (pin "2") (pinfunction "2_2") (pintype "passive"))
    )
    (net (code "38") (name "Net-(E1A-A6)") (class "Default")
      (node (ref "E1") (pin "7") (pinfunction "A6_7") (pintype "bidirectional"))
      (node (ref "R25") (pin "3") (pinfunction "3_3") (pintype "passive"))
    )
    (net (code "39") (name "Net-(E1A-A7)") (class "Default")
      (node (ref "E1") (pin "8") (pinfunction "A7_8") (pintype "bidirectional"))
      (node (ref "R25") (pin "4") (pinfunction "4_4") (pintype "passive"))
    )
    (net (code "40") (name "Net-(E1A-A8)") (class "Default")
      (node (ref "E1") (pin "9") (pinfunction "A8_9") (pintype "bidirectional"))
      (node (ref "R25") (pin "5") (pinfunction "5_5") (pintype "passive"))
    )
    (net (code "41") (name "Net-(E5A-Y0)") (class "Default")
      (node (ref "E5") (pin "15") (pinfunction "Y0_15") (pintype "output"))
      (node (ref "S1") (pin "1") (pinfunction "1_1") (pintype "passive"))
    )
    (net (code "42") (name "Net-(E5A-Y1)") (class "Default")
      (node (ref "E5") (pin "14") (pinfunction "Y1_14") (pintype "output"))
      (node (ref "S1") (pin "2") (pinfunction "2_2") (pintype "passive"))
    )
    (net (code "43") (name "Net-(E5A-Y2)") (class "Default")
      (node (ref "E5") (pin "13") (pinfunction "Y2_13") (pintype "output"))
      (node (ref "S1") (pin "3") (pinfunction "3_3") (pintype "passive"))
    )
    (net (code "44") (name "Net-(E5A-Y3)") (class "Default")
      (node (ref "E5") (pin "12") (pinfunction "Y3_12") (pintype "output"))
      (node (ref "S1") (pin "4") (pinfunction "4_4") (pintype "passive"))
    )
    (net (code "45") (name "Net-(E5A-Y4)") (class "Default")
      (node (ref "E5") (pin "11") (pinfunction "Y4_11") (pintype "output"))
      (node (ref "S1") (pin "5") (pinfunction "5_5") (pintype "passive"))
    )
    (net (code "46") (name "Net-(E5A-Y5)") (class "Default")
      (node (ref "E5") (pin "10") (pinfunction "Y5_10") (pintype "output"))
      (node (ref "S1") (pin "6") (pinfunction "6_6") (pintype "passive"))
    )
    (net (code "47") (name "Net-(E5A-Y6)") (class "Default")
      (node (ref "E5") (pin "9") (pinfunction "Y6_9") (pintype "output"))
      (node (ref "S1") (pin "7") (pinfunction "7_7") (pintype "passive"))
    )
    (net (code "48") (name "Net-(E5A-Y7)") (class "Default")
      (node (ref "E5") (pin "7") (pinfunction "Y7_7") (pintype "output"))
      (node (ref "S1") (pin "8") (pinfunction "8_8") (pintype "passive"))
    )
    (net (code "49") (name "Net-(E6A-I0)") (class "Default")
      (node (ref "E6") (pin "1") (pinfunction "I0_1") (pintype "input"))
      (node (ref "R23") (pin "3") (pinfunction "1_3") (pintype "passive"))
      (node (ref "S1") (pin "14") (pinfunction "14_14") (pintype "passive"))
    )
    (net (code "50") (name "Net-(E6A-I1)") (class "Default")
      (node (ref "E6") (pin "2") (pinfunction "I1_2") (pintype "input"))
      (node (ref "R23") (pin "4") (pinfunction "1_4") (pintype "passive"))
      (node (ref "S1") (pin "13") (pinfunction "13_13") (pintype "passive"))
    )
    (net (code "51") (name "Net-(E6A-I2)") (class "Default")
      (node (ref "E6") (pin "3") (pinfunction "I2_3") (pintype "input"))
      (node (ref "R23") (pin "5") (pinfunction "1_5") (pintype "passive"))
      (node (ref "S1") (pin "12") (pinfunction "12_12") (pintype "passive"))
    )
    (net (code "52") (name "Net-(E6A-I3)") (class "Default")
      (node (ref "E6") (pin "4") (pinfunction "I3_4") (pintype "input"))
      (node (ref "R23") (pin "6") (pinfunction "1_6") (pintype "passive"))
      (node (ref "S1") (pin "11") (pinfunction "11_11") (pintype "passive"))
    )
    (net (code "53") (name "Net-(E6A-I4)") (class "Default")
      (node (ref "E6") (pin "5") (pinfunction "I4_5") (pintype "input"))
      (node (ref "R23") (pin "7") (pinfunction "1_7") (pintype "passive"))
      (node (ref "S1") (pin "10") (pinfunction "10_10") (pintype "passive"))
    )
    (net (code "54") (name "Net-(E6A-I5)") (class "Default")
      (node (ref "E6") (pin "6") (pinfunction "I5_6") (pintype "input"))
      (node (ref "R23") (pin "8") (pinfunction "1_8") (pintype "passive"))
      (node (ref "S1") (pin "9") (pinfunction "9_9") (pintype "passive"))
    )
    (net (code "55") (name "Net-(E6A-I6)") (class "Default")
      (node (ref "E6") (pin "11") (pinfunction "I6_11") (pintype "input"))
      (node (ref "R23") (pin "2") (pinfunction "1_2") (pintype "passive"))
      (node (ref "S1") (pin "15") (pinfunction "15_15") (pintype "passive"))
    )
    (net (code "56") (name "Net-(E6A-I7)") (class "Default")
      (node (ref "E6") (pin "12") (pinfunction "I7_12") (pintype "input"))
      (node (ref "R23") (pin "1") (pinfunction "1_1") (pintype "passive"))
      (node (ref "S1") (pin "16") (pinfunction "16_16") (pintype "passive"))
    )
    (net (code "57") (name "Net-(Q1-B)") (class "Default")
      (node (ref "Q1") (pin "2") (pinfunction "B_2") (pintype "passive"))
      (node (ref "R10") (pin "2") (pinfunction "2_2") (pintype "passive"))
    )
    (net (code "58") (name "Net-(Q1-C)") (class "Default")
      (node (ref "Q1") (pin "3") (pinfunction "C_3") (pintype "passive"))
      (node (ref "R5") (pin "1") (pinfunction "1_1") (pintype "passive"))
    )
    (net (code "59") (name "Net-(Q2-B)") (class "Default")
      (node (ref "Q2") (pin "2") (pinfunction "B_2") (pintype "passive"))
      (node (ref "R11") (pin "2") (pinfunction "2_2") (pintype "passive"))
    )
    (net (code "60") (name "Net-(Q2-C)") (class "Default")
      (node (ref "Q2") (pin "3") (pinfunction "C_3") (pintype "passive"))
      (node (ref "R6") (pin "1") (pinfunction "1_1") (pintype "passive"))
    )
    (net (code "61") (name "Net-(Q3-B)") (class "Default")
      (node (ref "Q3") (pin "2") (pinfunction "B_2") (pintype "passive"))
      (node (ref "R24") (pin "2") (pinfunction "2_2") (pintype "passive"))
    )
    (net (code "62") (name "Net-(SW2-S)") (class "Default")
      (node (ref "R12") (pin "2") (pinfunction "2_2") (pintype "passive"))
      (node (ref "SW2") (pin "1") (pinfunction "S_1") (pintype "passive"))
      (node (ref "SW2") (pin "2") (pinfunction "S1_2") (pintype "passive"))
    )
    (net (code "63") (name "Net-(SW3A-2)") (class "Default")
      (node (ref "R9") (pin "2") (pinfunction "2_2") (pintype "passive"))
      (node (ref "SW3") (pin "8") (pinfunction "2_8") (pintype "passive"))
    )
    (net (code "64") (name "Net-(SW3B-2)") (class "Default")
      (node (ref "R8") (pin "2") (pinfunction "2_2") (pintype "passive"))
      (node (ref "SW3") (pin "7") (pinfunction "2_7") (pintype "passive"))
    )
    (net (code "65") (name "Net-(SW3C-2)") (class "Default")
      (node (ref "R4") (pin "2") (pinfunction "2_2") (pintype "passive"))
      (node (ref "SW3") (pin "6") (pinfunction "2_6") (pintype "passive"))
    )
    (net (code "66") (name "Net-(SW3D-2)") (class "Default")
      (node (ref "R3") (pin "2") (pinfunction "2_2") (pintype "passive"))
      (node (ref "SW3") (pin "5") (pinfunction "2_5") (pintype "passive"))
    )
    (net (code "67") (name "Net-(U1-PB6(XTAL1{slash}TOSC1))") (class "Default")
      (node (ref "C9") (pin "1") (pinfunction "1_1") (pintype "passive"))
      (node (ref "R18") (pin "1") (pinfunction "1_1") (pintype "passive"))
      (node (ref "U1") (pin "9") (pinfunction "PB6(XTAL1/TOSC1)_9") (pintype "bidirectional"))
      (node (ref "Y1") (pin "2") (pinfunction "2_2") (pintype "passive"))
    )
    (net (code "68") (name "Net-(U1-PB7(XTAL2{slash}TOSC2))") (class "Default")
      (node (ref "C7") (pin "1") (pinfunction "1_1") (pintype "passive"))
      (node (ref "R18") (pin "2") (pinfunction "2_2") (pintype "passive"))
      (node (ref "U1") (pin "10") (pinfunction "PB7(XTAL2/TOSC2)_10") (pintype "bidirectional"))
      (node (ref "Y1") (pin "1") (pinfunction "1_1") (pintype "passive"))
    )
    (net (code "69") (name "Net-(U1-PD0(RXD))") (class "Default")
      (node (ref "R16") (pin "1") (pinfunction "1_1") (pintype "passive"))
      (node (ref "U1") (pin "2") (pinfunction "PD0(RXD)_2") (pintype "bidirectional"))
    )
    (net (code "70") (name "Net-(U1-PD1(TXD))") (class "Default")
      (node (ref "R17") (pin "1") (pinfunction "1_1") (pintype "passive"))
      (node (ref "U1") (pin "3") (pinfunction "PD1(TXD)_3") (pintype "bidirectional"))
    )
    (net (code "71") (name "Net-(U8A-O)") (class "Default")
      (node (ref "U8") (pin "12") (pinfunction "O_12") (pintype "output"))
      (node (ref "U8") (pin "3") (pinfunction "I0_3") (pintype "input"))
      (node (ref "U8") (pin "4") (pinfunction "I1_4") (pintype "input"))
      (node (ref "U8") (pin "5") (pinfunction "I2_5") (pintype "input"))
    )
    (net (code "72") (name "Net-(U8C-I0)") (class "Default")
      (node (ref "U8") (pin "9") (pinfunction "I0_9") (pintype "input"))
      (node (ref "U9") (pin "8") (pinfunction "O_8") (pintype "output"))
    )
    (net (code "73") (name "Net-(U8C-I1)") (class "Default")
      (node (ref "U8") (pin "10") (pinfunction "I1_10") (pintype "input"))
      (node (ref "U9") (pin "6") (pinfunction "O_6") (pintype "output"))
    )
    (net (code "74") (name "Net-(U8C-O)") (class "Default")
      (node (ref "U8") (pin "8") (pinfunction "O_8") (pintype "output"))
      (node (ref "U9") (pin "13") (pinfunction "I1_13") (pintype "input"))
      (node (ref "U9") (pin "2") (pinfunction "I1_2") (pintype "input"))
    )
    (net (code "75") (name "Net-(U9A-O)") (class "Default")
      (node (ref "U9") (pin "12") (pinfunction "I0_12") (pintype "input"))
      (node (ref "U9") (pin "3") (pinfunction "O_3") (pintype "output"))
    )
    (net (code "76") (name "Net-(U10A-C1+)") (class "Default")
      (node (ref "C14") (pin "1") (pinfunction "1_1") (pintype "passive"))
      (node (ref "U10") (pin "1") (pinfunction "C1+_1") (pintype "bidirectional"))
    )
    (net (code "77") (name "Net-(U10A-C1-)") (class "Default")
      (node (ref "C14") (pin "2") (pinfunction "2_2") (pintype "passive"))
      (node (ref "U10") (pin "3") (pinfunction "C1-_3") (pintype "bidirectional"))
    )
    (net (code "78") (name "Net-(U10A-C2+)") (class "Default")
      (node (ref "C15") (pin "1") (pinfunction "1_1") (pintype "passive"))
      (node (ref "U10") (pin "4") (pinfunction "C2+_4") (pintype "bidirectional"))
    )
    (net (code "79") (name "Net-(U10A-C2-)") (class "Default")
      (node (ref "C15") (pin "2") (pinfunction "2_2") (pintype "passive"))
      (node (ref "U10") (pin "5") (pinfunction "C2-_5") (pintype "bidirectional"))
    )
    (net (code "80") (name "Net-(U10A-V+)") (class "Default")
      (node (ref "C16") (pin "1") (pinfunction "1_1") (pintype "passive"))
      (node (ref "U10") (pin "2") (pinfunction "V+_2") (pintype "bidirectional"))
    )
    (net (code "81") (name "Net-(U10A-V-)") (class "Default")
      (node (ref "C17") (pin "2") (pinfunction "2_2") (pintype "passive"))
      (node (ref "U10") (pin "6") (pinfunction "V-_6") (pintype "bidirectional"))
    )
    (net (code "82") (name "POWER_OK") (class "Default")
      (node (ref "J1") (pin "BV2") (pinfunction "1_BV2") (pintype "bidirectional"))
      (node (ref "R24") (pin "1") (pinfunction "1_1") (pintype "passive"))
    )
    (net (code "83") (name "PROG") (class "Default")
      (node (ref "C11") (pin "2") (pinfunction "2_2") (pintype "passive"))
      (node (ref "J2") (pin "1") (pinfunction "1_1") (pintype "passive"))
      (node (ref "R20") (pin "2") (pinfunction "2_2") (pintype "passive"))
      (node (ref "U10") (pin "11") (pinfunction "T1IN_11") (pintype "input"))
      (node (ref "U10") (pin "12") (pinfunction "R1OUT_12") (pintype "output"))
    )
    (net (code "84") (name "PULSE_LA") (class "Default")
      (node (ref "J1") (pin "DR2") (pinfunction "1_DR2") (pintype "bidirectional"))
      (node (ref "Q2") (pin "1") (pinfunction "E_1") (pintype "passive"))
    )
    (net (code "85") (name "RETURN") (class "Default")
      (node (ref "J1") (pin "AR2") (pinfunction "1_AR2") (pintype "bidirectional"))
    )
    (net (code "86") (name "RXD") (class "Default")
      (node (ref "J2") (pin "2") (pinfunction "2_2") (pintype "passive"))
      (node (ref "R16") (pin "2") (pinfunction "2_2") (pintype "passive"))
      (node (ref "U10") (pin "9") (pinfunction "R2OUT_9") (pintype "output"))
    )
    (net (code "87") (name "RXD232") (class "Default")
      (node (ref "J4") (pin "J") (pinfunction "8_J") (pintype "bidirectional"))
      (node (ref "J5") (pin "2") (pinfunction "F_2") (pintype "passive"))
      (node (ref "U10") (pin "8") (pinfunction "R2IN_8") (pintype "input"))
    )
    (net (code "88") (name "R_RUN") (class "Default")
      (node (ref "R2") (pin "1") (pinfunction "1_1") (pintype "passive"))
      (node (ref "U1") (pin "14") (pinfunction "PB0(ICP)_14") (pintype "bidirectional"))
    )
    (net (code "89") (name "R_SW") (class "Default")
      (node (ref "C10") (pin "1") (pinfunction "1_1") (pintype "passive"))
      (node (ref "R1") (pin "1") (pinfunction "1_1") (pintype "passive"))
      (node (ref "R12") (pin "1") (pinfunction "1_1") (pintype "passive"))
      (node (ref "U1") (pin "15") (pinfunction "PB1(OC1A)_15") (pintype "bidirectional"))
    )
    (net (code "90") (name "SCL") (class "Default")
      (node (ref "R22") (pin "1") (pinfunction "1_1") (pintype "passive"))
      (node (ref "U1") (pin "28") (pinfunction "PC5(ADC5/SCL)_28") (pintype "bidirectional"))
      (node (ref "U11") (pin "6") (pinfunction "SCL_6") (pintype "input"))
      (node (ref "U2") (pin "12") (pinfunction "SCL_12") (pintype "input"))
    )
    (net (code "91") (name "SDA") (class "Default")
      (node (ref "R21") (pin "1") (pinfunction "1_1") (pintype "passive"))
      (node (ref "U1") (pin "27") (pinfunction "PC4(ADC4/SDA)_27") (pintype "bidirectional"))
      (node (ref "U11") (pin "5") (pinfunction "SDA_5") (pintype "bidirectional"))
      (node (ref "U2") (pin "13") (pinfunction "SDA_13") (pintype "bidirectional"))
    )
    (net (code "92") (name "SET_FF") (class "Default")
      (node (ref "U1") (pin "4") (pinfunction "PD2(INT0)_4") (pintype "bidirectional"))
      (node (ref "U9") (pin "1") (pinfunction "I0_1") (pintype "input"))
    )
    (net (code "93") (name "SHOW_DATA") (class "Default")
      (node (ref "U1") (pin "5") (pinfunction "PD3(INT1)_5") (pintype "bidirectional"))
      (node (ref "U8") (pin "1") (pinfunction "I0_1") (pintype "input"))
    )
    (net (code "94") (name "SOURCE") (class "Default")
      (node (ref "E8") (pin "6") (pinfunction "A5_6") (pintype "input"))
      (node (ref "J1") (pin "AL2") (pinfunction "1_AL2") (pintype "bidirectional"))
    )
    (net (code "95") (name "STROBE") (class "Default")
      (node (ref "J1") (pin "AM2") (pinfunction "1_AM2") (pintype "bidirectional"))
    )
    (net (code "96") (name "SW") (class "Default")
      (node (ref "J1") (pin "DV2") (pinfunction "1_DV2") (pintype "bidirectional"))
      (node (ref "R1") (pin "2") (pinfunction "2_2") (pintype "passive"))
    )
    (net (code "97") (name "TP1") (class "Default")
      (node (ref "J1") (pin "CD2") (pinfunction "1_CD2") (pintype "bidirectional"))
    )
    (net (code "98") (name "TP2") (class "Default")
      (node (ref "J1") (pin "CE2") (pinfunction "1_CE2") (pintype "bidirectional"))
    )
    (net (code "99") (name "TP3") (class "Default")
      (node (ref "J1") (pin "CH2") (pinfunction "1_CH2") (pintype "bidirectional"))
    )
    (net (code "100") (name "TP4") (class "Default")
      (node (ref "J1") (pin "CJ2") (pinfunction "1_CJ2") (pintype "bidirectional"))
      (node (ref "U9") (pin "4") (pinfunction "I0_4") (pintype "input"))
      (node (ref "U9") (pin "5") (pinfunction "I1_5") (pintype "input"))
    )
    (net (code "101") (name "TXD") (class "Default")
      (node (ref "J2") (pin "3") (pinfunction "3_3") (pintype "passive"))
      (node (ref "R17") (pin "2") (pinfunction "2_2") (pintype "passive"))
      (node (ref "U10") (pin "10") (pinfunction "T2IN_10") (pintype "input"))
    )
    (net (code "102") (name "TXD232") (class "Default")
      (node (ref "J4") (pin "F") (pinfunction "6_F") (pintype "bidirectional"))
      (node (ref "J5") (pin "3") (pinfunction "F_3") (pintype "passive"))
      (node (ref "U10") (pin "7") (pinfunction "T2OUT_7") (pintype "output"))
    )
    (net (code "103") (name "V+") (class "Default")
      (node (ref "C20") (pin "1") (pinfunction "1_1") (pintype "passive"))
      (node (ref "C21") (pin "1") (pinfunction "1_1") (pintype "passive"))
      (node (ref "D2") (pin "C") (pinfunction "C_C") (pintype "passive"))
      (node (ref "D3") (pin "C") (pinfunction "C_C") (pintype "passive"))
      (node (ref "E3") (pin "28") (pinfunction "VCC_28") (pintype "power_in"))
      (node (ref "E4") (pin "28") (pinfunction "VCC_28") (pintype "power_in"))
      (node (ref "R15") (pin "2") (pinfunction "2_2") (pintype "passive"))
    )
    (net (code "104") (name "VCC") (class "Default")
      (node (ref "C1") (pin "1") (pinfunction "1_1") (pintype "passive"))
      (node (ref "C12") (pin "1") (pinfunction "1_1") (pintype "passive"))
      (node (ref "C13") (pin "1") (pinfunction "1_1") (pintype "passive"))
      (node (ref "C16") (pin "2") (pinfunction "2_2") (pintype "passive"))
      (node (ref "C18") (pin "1") (pinfunction "1_1") (pintype "passive"))
      (node (ref "C19") (pin "1") (pinfunction "1_1") (pintype "passive"))
      (node (ref "C2") (pin "1") (pinfunction "1_1") (pintype "passive"))
      (node (ref "C23") (pin "1") (pinfunction "1_1") (pintype "passive"))
      (node (ref "C24") (pin "1") (pinfunction "1_1") (pintype "passive"))
      (node (ref "C25") (pin "1") (pinfunction "1_1") (pintype "passive"))
      (node (ref "C26") (pin "1") (pinfunction "1_1") (pintype "passive"))
      (node (ref "C27") (pin "1") (pinfunction "1_1") (pintype "passive"))
      (node (ref "C28") (pin "1") (pinfunction "1_1") (pintype "passive"))
      (node (ref "C29") (pin "1") (pinfunction "1_1") (pintype "passive"))
      (node (ref "C3") (pin "1") (pinfunction "1_1") (pintype "passive"))
      (node (ref "C30") (pin "+") (pinfunction "+_+") (pintype "passive"))
      (node (ref "C4") (pin "1") (pinfunction "1_1") (pintype "passive"))
      (node (ref "C5") (pin "1") (pinfunction "1_1") (pintype "passive"))
      (node (ref "C6") (pin "1") (pinfunction "1_1") (pintype "passive"))
      (node (ref "C8") (pin "1") (pinfunction "1_1") (pintype "passive"))
      (node (ref "D1") (pin "C") (pinfunction "C_C") (pintype "passive"))
      (node (ref "D3") (pin "A") (pinfunction "A_A") (pintype "passive"))
      (node (ref "E7") (pin "1") (pinfunction "I0_1") (pintype "input"))
      (node (ref "E7") (pin "12") (pinfunction "I2_12") (pintype "input"))
      (node (ref "E7") (pin "13") (pinfunction "I3_13") (pintype "input"))
      (node (ref "J1") (pin "AA2") (pinfunction "1_AA2") (pintype "bidirectional"))
      (node (ref "J1") (pin "BA2") (pinfunction "1_BA2") (pintype "bidirectional"))
      (node (ref "J1") (pin "CA2") (pinfunction "1_CA2") (pintype "bidirectional"))
      (node (ref "J3") (pin "2") (pinfunction "2_2") (pintype "passive"))
      (node (ref "R13") (pin "2") (pinfunction "2_2") (pintype "passive"))
      (node (ref "R14") (pin "2") (pinfunction "2_2") (pintype "passive"))
      (node (ref "R19") (pin "2") (pinfunction "2_2") (pintype "passive"))
      (node (ref "R21") (pin "2") (pinfunction "2_2") (pintype "passive"))
      (node (ref "R22") (pin "2") (pinfunction "2_2") (pintype "passive"))
      (node (ref "R23") (pin "10") (pinfunction "2_10") (pintype "passive"))
      (node (ref "R23") (pin "11") (pinfunction "2_11") (pintype "passive"))
      (node (ref "R23") (pin "12") (pinfunction "2_12") (pintype "passive"))
      (node (ref "R23") (pin "13") (pinfunction "2_13") (pintype "passive"))
      (node (ref "R23") (pin "14") (pinfunction "2_14") (pintype "passive"))
      (node (ref "R23") (pin "15") (pinfunction "2_15") (pintype "passive"))
      (node (ref "R23") (pin "16") (pinfunction "2_16") (pintype "passive"))
      (node (ref "R23") (pin "9") (pinfunction "2_9") (pintype "passive"))
      (node (ref "R25") (pin "1") (pinfunction "1_1") (pintype "passive"))
      (node (ref "R5") (pin "2") (pinfunction "2_2") (pintype "passive"))
      (node (ref "R6") (pin "2") (pinfunction "2_2") (pintype "passive"))
      (node (ref "U1") (pin "20") (pinfunction "AVCC_20") (pintype "power_in"))
      (node (ref "U1") (pin "21") (pinfunction "AREF_21") (pintype "passive"))
      (node (ref "U1") (pin "7") (pinfunction "VCC_7") (pintype "power_in"))
      (node (ref "U11") (pin "8") (pinfunction "VCC_8") (pintype "power_in"))
      (node (ref "U2") (pin "18") (pinfunction "~{RESET}_18") (pintype "input"))
      (node (ref "U2") (pin "9") (pinfunction "VDD_9") (pintype "power_in"))
      (node (ref "U7") (pin "12") (pinfunction "I0_12") (pintype "input"))
      (node (ref "U7") (pin "13") (pinfunction "I1_13") (pintype "input"))
    )
    (net (code "105") (name "WRITE") (class "Default")
      (node (ref "E8") (pin "4") (pinfunction "A3_4") (pintype "input"))
      (node (ref "J1") (pin "AS2") (pinfunction "1_AS2") (pintype "bidirectional"))
    )
    (net (code "106") (name "W_DATA_00") (class "Default")
      (node (ref "U2") (pin "7") (pinfunction "GPB6_7") (pintype "bidirectional"))
      (node (ref "U3") (pin "1") (pinfunction "I0_1") (pintype "input"))
    )
    (net (code "107") (name "W_DATA_01") (class "Default")
      (node (ref "U2") (pin "6") (pinfunction "GPB5_6") (pintype "bidirectional"))
      (node (ref "U3") (pin "4") (pinfunction "I0_4") (pintype "input"))
    )
    (net (code "108") (name "W_DATA_02") (class "Default")
      (node (ref "U2") (pin "5") (pinfunction "GPB4_5") (pintype "bidirectional"))
      (node (ref "U3") (pin "12") (pinfunction "I0_12") (pintype "input"))
    )
    (net (code "109") (name "W_DATA_03") (class "Default")
      (node (ref "U2") (pin "3") (pinfunction "GPB2_3") (pintype "bidirectional"))
      (node (ref "U3") (pin "9") (pinfunction "I0_9") (pintype "input"))
    )
    (net (code "110") (name "W_DATA_04") (class "Default")
      (node (ref "U2") (pin "2") (pinfunction "GPB1_2") (pintype "bidirectional"))
      (node (ref "U4") (pin "1") (pinfunction "I0_1") (pintype "input"))
    )
    (net (code "111") (name "W_DATA_05") (class "Default")
      (node (ref "U2") (pin "1") (pinfunction "GPB0_1") (pintype "bidirectional"))
      (node (ref "U4") (pin "4") (pinfunction "I0_4") (pintype "input"))
    )
    (net (code "112") (name "W_DATA_06") (class "Default")
      (node (ref "U2") (pin "27") (pinfunction "GPA6_27") (pintype "bidirectional"))
      (node (ref "U4") (pin "12") (pinfunction "I0_12") (pintype "input"))
    )
    (net (code "113") (name "W_DATA_07") (class "Default")
      (node (ref "U2") (pin "26") (pinfunction "GPA5_26") (pintype "bidirectional"))
      (node (ref "U4") (pin "9") (pinfunction "I0_9") (pintype "input"))
    )
    (net (code "114") (name "W_DATA_08") (class "Default")
      (node (ref "U2") (pin "25") (pinfunction "GPA4_25") (pintype "bidirectional"))
      (node (ref "U5") (pin "1") (pinfunction "I0_1") (pintype "input"))
    )
    (net (code "115") (name "W_DATA_09") (class "Default")
      (node (ref "U2") (pin "23") (pinfunction "GPA2_23") (pintype "bidirectional"))
      (node (ref "U5") (pin "4") (pinfunction "I0_4") (pintype "input"))
    )
    (net (code "116") (name "W_DATA_10") (class "Default")
      (node (ref "U2") (pin "22") (pinfunction "GPA1_22") (pintype "bidirectional"))
      (node (ref "U5") (pin "12") (pinfunction "I0_12") (pintype "input"))
    )
    (net (code "117") (name "W_DATA_11") (class "Default")
      (node (ref "U2") (pin "21") (pinfunction "GPA0_21") (pintype "bidirectional"))
      (node (ref "U5") (pin "9") (pinfunction "I0_9") (pintype "input"))
    )
    (net (code "118") (name "W_INITIALIZE") (class "Default")
      (node (ref "R10") (pin "1") (pinfunction "1_1") (pintype "passive"))
      (node (ref "R13") (pin "1") (pinfunction "1_1") (pintype "passive"))
      (node (ref "U1") (pin "23") (pinfunction "PC0(ADC0)_23") (pintype "bidirectional"))
    )
    (net (code "119") (name "W_PULSE_LA") (class "Default")
      (node (ref "R11") (pin "1") (pinfunction "1_1") (pintype "passive"))
      (node (ref "R14") (pin "1") (pinfunction "1_1") (pintype "passive"))
      (node (ref "U1") (pin "24") (pinfunction "PC1(ADC1)_24") (pintype "bidirectional"))
    )
    (net (code "120") (name "W_STOP") (class "Default")
      (node (ref "U1") (pin "26") (pinfunction "PC3(ADC3)_26") (pintype "bidirectional"))
      (node (ref "U7") (pin "10") (pinfunction "I1_10") (pintype "input"))
      (node (ref "U7") (pin "9") (pinfunction "I0_9") (pintype "input"))
    )
    (net (code "121") (name "unconnected-(E8A-Y8-Pad11)") (class "Default")
      (node (ref "E8") (pin "11") (pinfunction "Y8_11") (pintype "tri_state"))
    )
    (net (code "122") (name "unconnected-(J1A-1-PadAA1)") (class "Default")
      (node (ref "J1") (pin "AA1") (pinfunction "1_AA1") (pintype "bidirectional"))
    )
    (net (code "123") (name "unconnected-(J1AK-1-PadBA1)") (class "Default")
      (node (ref "J1") (pin "BA1") (pinfunction "1_BA1") (pintype "bidirectional"))
    )
    (net (code "124") (name "unconnected-(J1AM-1-PadBB1)") (class "Default")
      (node (ref "J1") (pin "BB1") (pinfunction "1_BB1") (pintype "bidirectional"))
    )
    (net (code "125") (name "unconnected-(J1BN-1-PadBS2)") (class "Default")
      (node (ref "J1") (pin "BS2") (pinfunction "1_BS2") (pintype "bidirectional"))
    )
    (net (code "126") (name "unconnected-(J1BU-1-PadCA1)") (class "Default")
      (node (ref "J1") (pin "CA1") (pinfunction "1_CA1") (pintype "bidirectional"))
    )
    (net (code "127") (name "unconnected-(J1BW-1-PadCB1)") (class "Default")
      (node (ref "J1") (pin "CB1") (pinfunction "1_CB1") (pintype "bidirectional"))
    )
    (net (code "128") (name "unconnected-(J1C-1-PadAB1)") (class "Default")
      (node (ref "J1") (pin "AB1") (pinfunction "1_AB1") (pintype "bidirectional"))
    )
    (net (code "129") (name "unconnected-(J1DE-1-PadDA1)") (class "Default")
      (node (ref "J1") (pin "DA1") (pinfunction "1_DA1") (pintype "bidirectional"))
    )
    (net (code "130") (name "unconnected-(J1DG-1-PadDB1)") (class "Default")
      (node (ref "J1") (pin "DB1") (pinfunction "1_DB1") (pintype "bidirectional"))
    )
    (net (code "131") (name "unconnected-(J4-3-PadC)") (class "Default")
      (node (ref "J4") (pin "C") (pinfunction "3_C") (pintype "bidirectional"))
    )
    (net (code "132") (name "unconnected-(J4-4-PadD)") (class "Default")
      (node (ref "J4") (pin "D") (pinfunction "4_D") (pintype "bidirectional"))
    )
    (net (code "133") (name "unconnected-(J4-5-PadE)") (class "Default")
      (node (ref "J4") (pin "E") (pinfunction "5_E") (pintype "bidirectional"))
    )
    (net (code "134") (name "unconnected-(J4-7-PadH)") (class "Default")
      (node (ref "J4") (pin "H") (pinfunction "7_H") (pintype "bidirectional"))
    )
    (net (code "135") (name "unconnected-(J4-9-PadK)") (class "Default")
      (node (ref "J4") (pin "K") (pinfunction "9_K") (pintype "bidirectional"))
    )
    (net (code "136") (name "unconnected-(J4-10-PadL)") (class "Default")
      (node (ref "J4") (pin "L") (pinfunction "10_L") (pintype "bidirectional"))
    )
    (net (code "137") (name "unconnected-(J4-11-PadM)") (class "Default")
      (node (ref "J4") (pin "M") (pinfunction "11_M") (pintype "bidirectional"))
    )
    (net (code "138") (name "unconnected-(J4-12-PadN)") (class "Default")
      (node (ref "J4") (pin "N") (pinfunction "12_N") (pintype "bidirectional"))
    )
    (net (code "139") (name "unconnected-(J4-13-PadP)") (class "Default")
      (node (ref "J4") (pin "P") (pinfunction "13_P") (pintype "bidirectional"))
    )
    (net (code "140") (name "unconnected-(J4-14-PadR)") (class "Default")
      (node (ref "J4") (pin "R") (pinfunction "14_R") (pintype "bidirectional"))
    )
    (net (code "141") (name "unconnected-(J4-15-PadS)") (class "Default")
      (node (ref "J4") (pin "S") (pinfunction "15_S") (pintype "bidirectional"))
    )
    (net (code "142") (name "unconnected-(J4-16-PadT)") (class "Default")
      (node (ref "J4") (pin "T") (pinfunction "16_T") (pintype "bidirectional"))
    )
    (net (code "143") (name "unconnected-(J4-17-PadU)") (class "Default")
      (node (ref "J4") (pin "U") (pinfunction "17_U") (pintype "bidirectional"))
    )
    (net (code "144") (name "unconnected-(J4-18-PadV)") (class "Default")
      (node (ref "J4") (pin "V") (pinfunction "18_V") (pintype "bidirectional"))
    )
    (net (code "145") (name "unconnected-(J4-19-PadW)") (class "Default")
      (node (ref "J4") (pin "W") (pinfunction "19_W") (pintype "bidirectional"))
    )
    (net (code "146") (name "unconnected-(J4-20-PadX)") (class "Default")
      (node (ref "J4") (pin "X") (pinfunction "20_X") (pintype "bidirectional"))
    )
    (net (code "147") (name "unconnected-(J4-21-PadY)") (class "Default")
      (node (ref "J4") (pin "Y") (pinfunction "21_Y") (pintype "bidirectional"))
    )
    (net (code "148") (name "unconnected-(J4-23-PadAA)") (class "Default")
      (node (ref "J4") (pin "AA") (pinfunction "23_AA") (pintype "bidirectional"))
    )
    (net (code "149") (name "unconnected-(J4-24-PadBB)") (class "Default")
      (node (ref "J4") (pin "BB") (pinfunction "24_BB") (pintype "bidirectional"))
    )
    (net (code "150") (name "unconnected-(J4-25-PadCC)") (class "Default")
      (node (ref "J4") (pin "CC") (pinfunction "25_CC") (pintype "bidirectional"))
    )
    (net (code "151") (name "unconnected-(J4-26-PadDD)") (class "Default")
      (node (ref "J4") (pin "DD") (pinfunction "26_DD") (pintype "bidirectional"))
    )
    (net (code "152") (name "unconnected-(J4-27-PadEE)") (class "Default")
      (node (ref "J4") (pin "EE") (pinfunction "27_EE") (pintype "bidirectional"))
    )
    (net (code "153") (name "unconnected-(J4-28-PadFF)") (class "Default")
      (node (ref "J4") (pin "FF") (pinfunction "28_FF") (pintype "bidirectional"))
    )
    (net (code "154") (name "unconnected-(J4-29-PadHH)") (class "Default")
      (node (ref "J4") (pin "HH") (pinfunction "29_HH") (pintype "bidirectional"))
    )
    (net (code "155") (name "unconnected-(J4-30-PadJJ)") (class "Default")
      (node (ref "J4") (pin "JJ") (pinfunction "30_JJ") (pintype "bidirectional"))
    )
    (net (code "156") (name "unconnected-(J4-31-PadKK)") (class "Default")
      (node (ref "J4") (pin "KK") (pinfunction "31_KK") (pintype "bidirectional"))
    )
    (net (code "157") (name "unconnected-(J4-32-PadLL)") (class "Default")
      (node (ref "J4") (pin "LL") (pinfunction "32_LL") (pintype "bidirectional"))
    )
    (net (code "158") (name "unconnected-(J4-33-PadMM)") (class "Default")
      (node (ref "J4") (pin "MM") (pinfunction "33_MM") (pintype "bidirectional"))
    )
    (net (code "159") (name "unconnected-(J4-34-PadNN)") (class "Default")
      (node (ref "J4") (pin "NN") (pinfunction "34_NN") (pintype "bidirectional"))
    )
    (net (code "160") (name "unconnected-(J4-35-PadPP)") (class "Default")
      (node (ref "J4") (pin "PP") (pinfunction "35_PP") (pintype "bidirectional"))
    )
    (net (code "161") (name "unconnected-(J4-36-PadRR)") (class "Default")
      (node (ref "J4") (pin "RR") (pinfunction "36_RR") (pintype "bidirectional"))
    )
    (net (code "162") (name "unconnected-(U2-GPA3-Pad24)") (class "Default")
      (node (ref "U2") (pin "24") (pinfunction "GPA3_24") (pintype "bidirectional"))
    )
    (net (code "163") (name "unconnected-(U2-GPA7-Pad28)") (class "Default")
      (node (ref "U2") (pin "28") (pinfunction "GPA7_28") (pintype "bidirectional"))
    )
    (net (code "164") (name "unconnected-(U2-GPB3-Pad4)") (class "Default")
      (node (ref "U2") (pin "4") (pinfunction "GPB3_4") (pintype "bidirectional"))
    )
    (net (code "165") (name "unconnected-(U2-GPB7-Pad8)") (class "Default")
      (node (ref "U2") (pin "8") (pinfunction "GPB7_8") (pintype "bidirectional"))
    )
    (net (code "166") (name "unconnected-(U2-INTA-Pad20)") (class "Default")
      (node (ref "U2") (pin "20") (pinfunction "INTA_20") (pintype "output"))
    )
    (net (code "167") (name "unconnected-(U2-INTB-Pad19)") (class "Default")
      (node (ref "U2") (pin "19") (pinfunction "INTB_19") (pintype "output"))
    )
    (net (code "168") (name "unconnected-(U7D-O-Pad11)") (class "Default")
      (node (ref "U7") (pin "11") (pinfunction "O_11") (pintype "open_collector"))
    )
    (net (code "169") (name "unconnected-(U10A-T1OUT-Pad14)") (class "Default")
      (node (ref "U10") (pin "14") (pinfunction "T1OUT_14") (pintype "output"))
    )
    (net (code "170") (name "~{BDISABLE}") (class "Default")
      (node (ref "E7") (pin "10") (pinfunction "I1_10") (pintype "input"))
      (node (ref "E8") (pin "18") (pinfunction "Y1_18") (pintype "tri_state"))
    )
    (net (code "171") (name "~{BMD_DIR}") (class "Default")
      (node (ref "E7") (pin "2") (pinfunction "I1_2") (pintype "input"))
      (node (ref "E8") (pin "17") (pinfunction "Y2_17") (pintype "tri_state"))
    )
    (net (code "172") (name "~{BREAK_CYCLE}") (class "Default")
      (node (ref "J1") (pin "BL2") (pinfunction "1_BL2") (pintype "bidirectional"))
    )
    (net (code "173") (name "~{BRK_DATA}") (class "Default")
      (node (ref "J1") (pin "BK2") (pinfunction "1_BK2") (pintype "bidirectional"))
      (node (ref "U7") (pin "3") (pinfunction "O_3") (pintype "open_collector"))
    )
    (net (code "174") (name "~{BRK_IN_PROG}") (class "Default")
      (node (ref "J1") (pin "BE2") (pinfunction "1_BE2") (pintype "bidirectional"))
    )
    (net (code "175") (name "~{BSOURCE}") (class "Default")
      (node (ref "E8") (pin "14") (pinfunction "Y5_14") (pintype "tri_state"))
      (node (ref "E8") (pin "7") (pinfunction "A6_7") (pintype "input"))
    )
    (net (code "176") (name "~{BUS_STROBE}") (class "Default")
      (node (ref "J1") (pin "CK1") (pinfunction "1_CK1") (pintype "bidirectional"))
    )
    (net (code "177") (name "~{BWRITE}") (class "Default")
      (node (ref "E8") (pin "16") (pinfunction "Y3_16") (pintype "tri_state"))
      (node (ref "E8") (pin "5") (pinfunction "A4_5") (pintype "input"))
    )
    (net (code "178") (name "~{C0}") (class "Default")
      (node (ref "J1") (pin "CE1") (pinfunction "1_CE1") (pintype "bidirectional"))
    )
    (net (code "179") (name "~{C1}") (class "Default")
      (node (ref "J1") (pin "CH1") (pinfunction "1_CH1") (pintype "bidirectional"))
    )
    (net (code "180") (name "~{C2}") (class "Default")
      (node (ref "J1") (pin "CJ1") (pinfunction "1_CJ1") (pintype "bidirectional"))
    )
    (net (code "181") (name "~{CE}") (class "Default")
      (node (ref "C22") (pin "1") (pinfunction "1_1") (pintype "passive"))
      (node (ref "E3") (pin "20") (pinfunction "~{CE}_20") (pintype "input"))
      (node (ref "E4") (pin "20") (pinfunction "~{CE}_20") (pintype "input"))
      (node (ref "Q3") (pin "1") (pinfunction "C_1") (pintype "passive"))
      (node (ref "R15") (pin "1") (pinfunction "1_1") (pintype "passive"))
    )
    (net (code "182") (name "~{CPMA_DISABLE}") (class "Default")
      (node (ref "J1") (pin "CU1") (pinfunction "1_CU1") (pintype "bidirectional"))
    )
    (net (code "183") (name "~{DATA00}") (class "Default")
      (node (ref "J1") (pin "AR1") (pinfunction "1_AR1") (pintype "bidirectional"))
      (node (ref "U3") (pin "3") (pinfunction "O_3") (pintype "open_collector"))
    )
    (net (code "184") (name "~{DATA01}") (class "Default")
      (node (ref "J1") (pin "AS1") (pinfunction "1_AS1") (pintype "bidirectional"))
      (node (ref "U3") (pin "6") (pinfunction "O_6") (pintype "open_collector"))
    )
    (net (code "185") (name "~{DATA02}") (class "Default")
      (node (ref "J1") (pin "AU1") (pinfunction "1_AU1") (pintype "bidirectional"))
      (node (ref "U3") (pin "11") (pinfunction "O_11") (pintype "open_collector"))
    )
    (net (code "186") (name "~{DATA03}") (class "Default")
      (node (ref "J1") (pin "AV1") (pinfunction "1_AV1") (pintype "bidirectional"))
      (node (ref "U3") (pin "8") (pinfunction "O_8") (pintype "open_collector"))
    )
    (net (code "187") (name "~{DATA04}") (class "Default")
      (node (ref "J1") (pin "BR1") (pinfunction "1_BR1") (pintype "bidirectional"))
      (node (ref "U4") (pin "3") (pinfunction "O_3") (pintype "open_collector"))
    )
    (net (code "188") (name "~{DATA05}") (class "Default")
      (node (ref "J1") (pin "BS1") (pinfunction "1_BS1") (pintype "bidirectional"))
      (node (ref "U4") (pin "6") (pinfunction "O_6") (pintype "open_collector"))
    )
    (net (code "189") (name "~{DATA06}") (class "Default")
      (node (ref "J1") (pin "BU1") (pinfunction "1_BU1") (pintype "bidirectional"))
      (node (ref "U4") (pin "11") (pinfunction "O_11") (pintype "open_collector"))
    )
    (net (code "190") (name "~{DATA07}") (class "Default")
      (node (ref "J1") (pin "BV1") (pinfunction "1_BV1") (pintype "bidirectional"))
      (node (ref "U4") (pin "8") (pinfunction "O_8") (pintype "open_collector"))
    )
    (net (code "191") (name "~{DATA08}") (class "Default")
      (node (ref "J1") (pin "DR1") (pinfunction "1_DR1") (pintype "bidirectional"))
      (node (ref "U5") (pin "3") (pinfunction "O_3") (pintype "open_collector"))
    )
    (net (code "192") (name "~{DATA09}") (class "Default")
      (node (ref "J1") (pin "DS1") (pinfunction "1_DS1") (pintype "bidirectional"))
      (node (ref "U5") (pin "6") (pinfunction "O_6") (pintype "open_collector"))
    )
    (net (code "193") (name "~{DATA10}") (class "Default")
      (node (ref "J1") (pin "DU1") (pinfunction "1_DU1") (pintype "bidirectional"))
      (node (ref "U5") (pin "11") (pinfunction "O_11") (pintype "open_collector"))
    )
    (net (code "194") (name "~{DATA11}") (class "Default")
      (node (ref "J1") (pin "DV1") (pinfunction "1_DV1") (pintype "bidirectional"))
      (node (ref "U5") (pin "8") (pinfunction "O_8") (pintype "open_collector"))
    )
    (net (code "195") (name "~{D}") (class "Default")
      (node (ref "J1") (pin "DK2") (pinfunction "1_DK2") (pintype "bidirectional"))
    )
    (net (code "196") (name "~{EMA0}") (class "Default")
      (node (ref "E3") (pin "8") (pinfunction "A2_8") (pintype "input"))
      (node (ref "E4") (pin "8") (pinfunction "A2_8") (pintype "input"))
      (node (ref "E5") (pin "3") (pinfunction "C_3") (pintype "input"))
      (node (ref "J1") (pin "AD2") (pinfunction "1_AD2") (pintype "bidirectional"))
    )
    (net (code "197") (name "~{EMA1}") (class "Default")
      (node (ref "E3") (pin "9") (pinfunction "A1_9") (pintype "input"))
      (node (ref "E4") (pin "9") (pinfunction "A1_9") (pintype "input"))
      (node (ref "E5") (pin "2") (pinfunction "B_2") (pintype "input"))
      (node (ref "J1") (pin "AE2") (pinfunction "1_AE2") (pintype "bidirectional"))
    )
    (net (code "198") (name "~{EMA2}") (class "Default")
      (node (ref "E3") (pin "10") (pinfunction "A0_10") (pintype "input"))
      (node (ref "E4") (pin "10") (pinfunction "A0_10") (pintype "input"))
      (node (ref "E5") (pin "1") (pinfunction "A_1") (pintype "input"))
      (node (ref "J1") (pin "AH2") (pinfunction "1_AH2") (pintype "bidirectional"))
    )
    (net (code "199") (name "~{E}") (class "Default")
      (node (ref "J1") (pin "DL2") (pinfunction "1_DL2") (pintype "bidirectional"))
    )
    (net (code "200") (name "~{FSET}") (class "Default")
      (node (ref "J1") (pin "DP2") (pinfunction "1_DP2") (pintype "bidirectional"))
    )
    (net (code "201") (name "~{F}") (class "Default")
      (node (ref "J1") (pin "DJ2") (pinfunction "1_DJ2") (pintype "bidirectional"))
    )
    (net (code "202") (name "~{IND1}") (class "Default")
      (node (ref "J1") (pin "CU2") (pinfunction "1_CU2") (pintype "bidirectional"))
    )
    (net (code "203") (name "~{IND2}") (class "Default")
      (node (ref "J1") (pin "CV2") (pinfunction "1_CV2") (pintype "bidirectional"))
    )
    (net (code "204") (name "~{INTERNAL_IO}") (class "Default")
      (node (ref "J1") (pin "CL1") (pinfunction "1_CL1") (pintype "bidirectional"))
    )
    (net (code "205") (name "~{INT_RQST}") (class "Default")
      (node (ref "J1") (pin "CP1") (pinfunction "1_CP1") (pintype "bidirectional"))
    )
    (net (code "206") (name "~{IO_PAUSE}") (class "Default")
      (node (ref "J1") (pin "CD1") (pinfunction "1_CD1") (pintype "bidirectional"))
    )
    (net (code "207") (name "~{IR0}") (class "Default")
      (node (ref "J1") (pin "DD2") (pinfunction "1_DD2") (pintype "bidirectional"))
    )
    (net (code "208") (name "~{IR1}") (class "Default")
      (node (ref "J1") (pin "DE2") (pinfunction "1_DE2") (pintype "bidirectional"))
    )
    (net (code "209") (name "~{IR2}") (class "Default")
      (node (ref "J1") (pin "DH2") (pinfunction "1_DH2") (pintype "bidirectional"))
    )
    (net (code "210") (name "~{KEY_CONT}") (class "Default")
      (node (ref "J1") (pin "DU2") (pinfunction "1_DU2") (pintype "bidirectional"))
      (node (ref "U6") (pin "11") (pinfunction "O_11") (pintype "open_collector"))
    )
    (net (code "211") (name "~{LA_ENABLE}") (class "Default")
      (node (ref "J1") (pin "BM2") (pinfunction "1_BM2") (pintype "bidirectional"))
      (node (ref "U6") (pin "6") (pinfunction "O_6") (pintype "open_collector"))
    )
    (net (code "212") (name "~{LINK_DATA}") (class "Default")
      (node (ref "J1") (pin "CR2") (pinfunction "1_CR2") (pintype "bidirectional"))
    )
    (net (code "213") (name "~{LINK_LOAD}") (class "Default")
      (node (ref "J1") (pin "CS2") (pinfunction "1_CS2") (pintype "bidirectional"))
    )
    (net (code "214") (name "~{LINK}") (class "Default")
      (node (ref "J1") (pin "AV2") (pinfunction "1_AV2") (pintype "bidirectional"))
    )
    (net (code "215") (name "~{LOAD_CONT}") (class "Default")
      (node (ref "J1") (pin "BH2") (pinfunction "1_BH2") (pintype "bidirectional"))
    )
    (net (code "216") (name "~{MA00}") (class "Default")
      (node (ref "E3") (pin "21") (pinfunction "A10_21") (pintype "input"))
      (node (ref "E4") (pin "21") (pinfunction "A10_21") (pintype "input"))
      (node (ref "J1") (pin "AD1") (pinfunction "1_AD1") (pintype "bidirectional"))
    )
    (net (code "217") (name "~{MA01}") (class "Default")
      (node (ref "E3") (pin "23") (pinfunction "A11_23") (pintype "input"))
      (node (ref "E4") (pin "23") (pinfunction "A11_23") (pintype "input"))
      (node (ref "J1") (pin "AE1") (pinfunction "1_AE1") (pintype "bidirectional"))
    )
    (net (code "218") (name "~{MA02}") (class "Default")
      (node (ref "E3") (pin "24") (pinfunction "A9_24") (pintype "input"))
      (node (ref "E4") (pin "24") (pinfunction "A9_24") (pintype "input"))
      (node (ref "J1") (pin "AH1") (pinfunction "1_AH1") (pintype "bidirectional"))
    )
    (net (code "219") (name "~{MA03}") (class "Default")
      (node (ref "E3") (pin "25") (pinfunction "A8_25") (pintype "input"))
      (node (ref "E4") (pin "25") (pinfunction "A8_25") (pintype "input"))
      (node (ref "J1") (pin "AJ1") (pinfunction "1_AJ1") (pintype "bidirectional"))
    )
    (net (code "220") (name "~{MA04}") (class "Default")
      (node (ref "E3") (pin "26") (pinfunction "A13_26") (pintype "input"))
      (node (ref "E4") (pin "26") (pinfunction "A13_26") (pintype "input"))
      (node (ref "J1") (pin "BD1") (pinfunction "1_BD1") (pintype "bidirectional"))
    )
    (net (code "221") (name "~{MA05}") (class "Default")
      (node (ref "E3") (pin "1") (pinfunction "A14_1") (pintype "input"))
      (node (ref "E4") (pin "1") (pinfunction "A14_1") (pintype "input"))
      (node (ref "J1") (pin "BE1") (pinfunction "1_BE1") (pintype "bidirectional"))
    )
    (net (code "222") (name "~{MA06}") (class "Default")
      (node (ref "E3") (pin "2") (pinfunction "A12_2") (pintype "input"))
      (node (ref "E4") (pin "2") (pinfunction "A12_2") (pintype "input"))
      (node (ref "J1") (pin "BH1") (pinfunction "1_BH1") (pintype "bidirectional"))
    )
    (net (code "223") (name "~{MA07}") (class "Default")
      (node (ref "E3") (pin "3") (pinfunction "A7_3") (pintype "input"))
      (node (ref "E4") (pin "3") (pinfunction "A7_3") (pintype "input"))
      (node (ref "J1") (pin "BJ1") (pinfunction "1_BJ1") (pintype "bidirectional"))
    )
    (net (code "224") (name "~{MA08}") (class "Default")
      (node (ref "E3") (pin "4") (pinfunction "A6_4") (pintype "input"))
      (node (ref "E4") (pin "4") (pinfunction "A6_4") (pintype "input"))
      (node (ref "J1") (pin "DD1") (pinfunction "1_DD1") (pintype "bidirectional"))
    )
    (net (code "225") (name "~{MA09}") (class "Default")
      (node (ref "E3") (pin "5") (pinfunction "A5_5") (pintype "input"))
      (node (ref "E4") (pin "5") (pinfunction "A5_5") (pintype "input"))
      (node (ref "J1") (pin "DE1") (pinfunction "1_DE1") (pintype "bidirectional"))
    )
    (net (code "226") (name "~{MA10}") (class "Default")
      (node (ref "E3") (pin "6") (pinfunction "A4_6") (pintype "input"))
      (node (ref "E4") (pin "6") (pinfunction "A4_6") (pintype "input"))
      (node (ref "J1") (pin "DH1") (pinfunction "1_DH1") (pintype "bidirectional"))
    )
    (net (code "227") (name "~{MA11}") (class "Default")
      (node (ref "E3") (pin "7") (pinfunction "A3_7") (pintype "input"))
      (node (ref "E4") (pin "7") (pinfunction "A3_7") (pintype "input"))
      (node (ref "J1") (pin "DJ1") (pinfunction "1_DJ1") (pintype "bidirectional"))
    )
    (net (code "228") (name "~{MD00}") (class "Default")
      (node (ref "E1") (pin "2") (pinfunction "A1_2") (pintype "bidirectional"))
      (node (ref "J1") (pin "AK1") (pinfunction "1_AK1") (pintype "bidirectional"))
    )
    (net (code "229") (name "~{MD01}") (class "Default")
      (node (ref "E1") (pin "3") (pinfunction "A2_3") (pintype "bidirectional"))
      (node (ref "J1") (pin "AL1") (pinfunction "1_AL1") (pintype "bidirectional"))
    )
    (net (code "230") (name "~{MD02}") (class "Default")
      (node (ref "E1") (pin "4") (pinfunction "A3_4") (pintype "bidirectional"))
      (node (ref "J1") (pin "AM1") (pinfunction "1_AM1") (pintype "bidirectional"))
    )
    (net (code "231") (name "~{MD03}") (class "Default")
      (node (ref "E1") (pin "5") (pinfunction "A4_5") (pintype "bidirectional"))
      (node (ref "J1") (pin "AP1") (pinfunction "1_AP1") (pintype "bidirectional"))
    )
    (net (code "232") (name "~{MD04}") (class "Default")
      (node (ref "E2") (pin "2") (pinfunction "A1_2") (pintype "bidirectional"))
      (node (ref "J1") (pin "BK1") (pinfunction "1_BK1") (pintype "bidirectional"))
    )
    (net (code "233") (name "~{MD05}") (class "Default")
      (node (ref "E2") (pin "3") (pinfunction "A2_3") (pintype "bidirectional"))
      (node (ref "J1") (pin "BL1") (pinfunction "1_BL1") (pintype "bidirectional"))
    )
    (net (code "234") (name "~{MD06}") (class "Default")
      (node (ref "E2") (pin "4") (pinfunction "A3_4") (pintype "bidirectional"))
      (node (ref "J1") (pin "BM1") (pinfunction "1_BM1") (pintype "bidirectional"))
    )
    (net (code "235") (name "~{MD07}") (class "Default")
      (node (ref "E2") (pin "5") (pinfunction "A4_5") (pintype "bidirectional"))
      (node (ref "J1") (pin "BP1") (pinfunction "1_BP1") (pintype "bidirectional"))
    )
    (net (code "236") (name "~{MD08}") (class "Default")
      (node (ref "E2") (pin "6") (pinfunction "A5_6") (pintype "bidirectional"))
      (node (ref "J1") (pin "DK1") (pinfunction "1_DK1") (pintype "bidirectional"))
    )
    (net (code "237") (name "~{MD09}") (class "Default")
      (node (ref "E2") (pin "7") (pinfunction "A6_7") (pintype "bidirectional"))
      (node (ref "J1") (pin "DL1") (pinfunction "1_DL1") (pintype "bidirectional"))
    )
    (net (code "238") (name "~{MD10}") (class "Default")
      (node (ref "E2") (pin "8") (pinfunction "A7_8") (pintype "bidirectional"))
      (node (ref "J1") (pin "DM1") (pinfunction "1_DM1") (pintype "bidirectional"))
    )
    (net (code "239") (name "~{MD11}") (class "Default")
      (node (ref "E2") (pin "9") (pinfunction "A8_9") (pintype "bidirectional"))
      (node (ref "J1") (pin "DP1") (pinfunction "1_DP1") (pintype "bidirectional"))
    )
    (net (code "240") (name "~{MD_DIR}") (class "Default")
      (node (ref "E8") (pin "8") (pinfunction "A7_8") (pintype "input"))
      (node (ref "J1") (pin "AK2") (pinfunction "1_AK2") (pintype "bidirectional"))
      (node (ref "U7") (pin "6") (pinfunction "O_6") (pintype "open_collector"))
    )
    (net (code "241") (name "~{MEM_START}") (class "Default")
      (node (ref "J1") (pin "AJ2") (pinfunction "1_AJ2") (pintype "bidirectional"))
      (node (ref "U6") (pin "3") (pinfunction "O_3") (pintype "open_collector"))
    )
    (net (code "242") (name "~{MS_DISABLE}") (class "Default")
      (node (ref "J1") (pin "CV1") (pinfunction "1_CV1") (pintype "bidirectional"))
      (node (ref "U6") (pin "8") (pinfunction "O_8") (pintype "open_collector"))
    )
    (net (code "243") (name "~{NOT_LAST_TR}") (class "Default")
      (node (ref "J1") (pin "CM1") (pinfunction "1_CM1") (pintype "bidirectional"))
    )
    (net (code "244") (name "~{NTS_STALL}") (class "Default")
      (node (ref "J1") (pin "BR2") (pinfunction "1_BR2") (pintype "bidirectional"))
    )
    (net (code "245") (name "~{OVERFLOW}") (class "Default")
      (node (ref "J1") (pin "BJ2") (pinfunction "1_BJ2") (pintype "bidirectional"))
    )
    (net (code "246") (name "~{READ_EN}") (class "Default")
      (node (ref "E1") (pin "1") (pinfunction "DIR_1") (pintype "input"))
      (node (ref "E2") (pin "1") (pinfunction "DIR_1") (pintype "input"))
      (node (ref "E3") (pin "22") (pinfunction "~{OE}_22") (pintype "input"))
      (node (ref "E4") (pin "22") (pinfunction "~{OE}_22") (pintype "input"))
      (node (ref "E7") (pin "8") (pinfunction "O_8") (pintype "output"))
    )
    (net (code "247") (name "~{RESET}") (class "Default")
      (node (ref "C11") (pin "1") (pinfunction "1_1") (pintype "passive"))
      (node (ref "D1") (pin "A") (pinfunction "A_A") (pintype "passive"))
      (node (ref "J3") (pin "5") (pinfunction "5_5") (pintype "passive"))
      (node (ref "R19") (pin "1") (pinfunction "1_1") (pintype "passive"))
      (node (ref "U1") (pin "1") (pinfunction "PC6(/RESET)_1") (pintype "bidirectional"))
    )
    (net (code "248") (name "~{ROM_ADDR}") (class "Default")
      (node (ref "E5") (pin "6") (pinfunction "G1_6") (pintype "input"))
      (node (ref "J1") (pin "AU2") (pinfunction "1_AU2") (pintype "bidirectional"))
    )
    (net (code "249") (name "~{RUN}") (class "Default")
      (node (ref "J1") (pin "BU2") (pinfunction "1_BU2") (pintype "bidirectional"))
      (node (ref "R2") (pin "2") (pinfunction "2_2") (pintype "passive"))
    )
    (net (code "250") (name "~{SKIP}") (class "Default")
      (node (ref "J1") (pin "CS1") (pinfunction "1_CS1") (pintype "bidirectional"))
    )
    (net (code "251") (name "~{STOP}") (class "Default")
      (node (ref "J1") (pin "DS2") (pinfunction "1_DS2") (pintype "bidirectional"))
      (node (ref "U7") (pin "8") (pinfunction "O_8") (pintype "open_collector"))
    )
    (net (code "252") (name "~{TS1}") (class "Default")
      (node (ref "J1") (pin "CK2") (pinfunction "1_CK2") (pintype "bidirectional"))
    )
    (net (code "253") (name "~{TS2}") (class "Default")
      (node (ref "J1") (pin "CL2") (pinfunction "1_CL2") (pintype "bidirectional"))
    )
    (net (code "254") (name "~{TS3}") (class "Default")
      (node (ref "J1") (pin "CM2") (pinfunction "1_CM2") (pintype "bidirectional"))
    )
    (net (code "255") (name "~{TS4}") (class "Default")
      (node (ref "J1") (pin "CP2") (pinfunction "1_CP2") (pintype "bidirectional"))
      (node (ref "U8") (pin "13") (pinfunction "I2_13") (pintype "input"))
    )
    (net (code "256") (name "~{USER_MODE}") (class "Default")
      (node (ref "J1") (pin "DM2") (pinfunction "1_DM2") (pintype "bidirectional"))
    )
    (net (code "257") (name "~{WRITE_EN}") (class "Default")
      (node (ref "E3") (pin "27") (pinfunction "~{WE}_27") (pintype "input"))
      (node (ref "E4") (pin "27") (pinfunction "~{WE}_27") (pintype "input"))
      (node (ref "E7") (pin "6") (pinfunction "O_6") (pintype "output"))
    )
    (net (code "258") (name "~{W_KEY_CONTROL}") (class "Default")
      (node (ref "U1") (pin "13") (pinfunction "PD7(AIN1)_13") (pintype "bidirectional"))
      (node (ref "U6") (pin "12") (pinfunction "I0_12") (pintype "input"))
    )
    (net (code "259") (name "~{W_LA_ENABLE}") (class "Default")
      (node (ref "U1") (pin "11") (pinfunction "PD5(T1)_11") (pintype "bidirectional"))
      (node (ref "U6") (pin "4") (pinfunction "I0_4") (pintype "input"))
    )
    (net (code "260") (name "~{W_MEM_START}") (class "Default")
      (node (ref "R7") (pin "2") (pinfunction "2_2") (pintype "passive"))
      (node (ref "U1") (pin "25") (pinfunction "PC2(ADC2)_25") (pintype "bidirectional"))
      (node (ref "U6") (pin "1") (pinfunction "I0_1") (pintype "input"))
      (node (ref "U6") (pin "2") (pinfunction "I1_2") (pintype "input"))
    )
    (net (code "261") (name "~{W_MS_IR_DISABLE}") (class "Default")
      (node (ref "U1") (pin "12") (pinfunction "PD6(AIN0)_12") (pintype "bidirectional"))
      (node (ref "U6") (pin "9") (pinfunction "I0_9") (pintype "input"))
    )
  )
)
